# M_2_SoM_breakout_board_v0_3.net
KiCad netlist of a schematic drawn in EAGLE
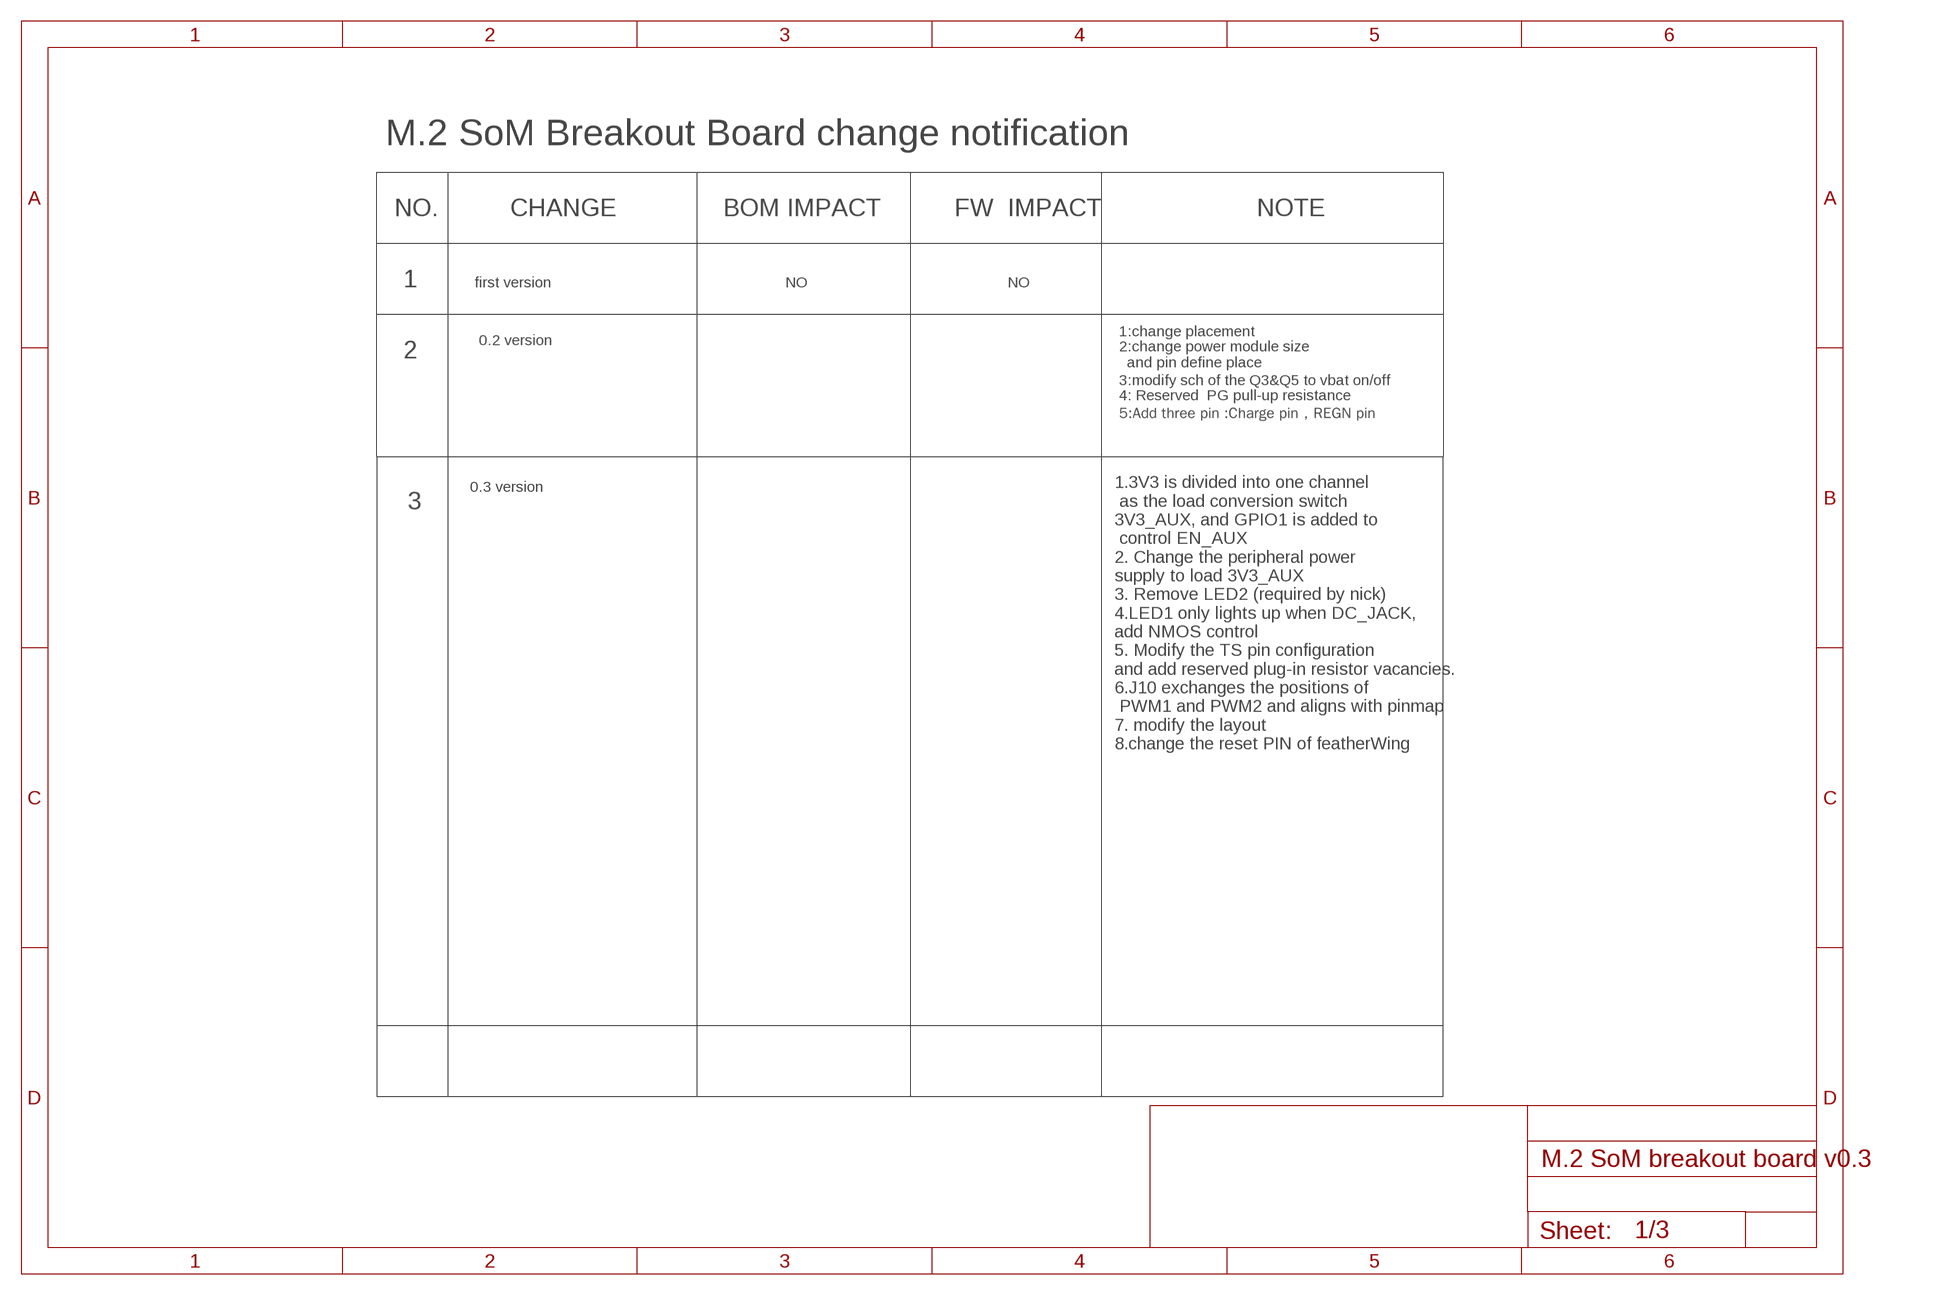
[diagram p0: schematic, sheet 1]
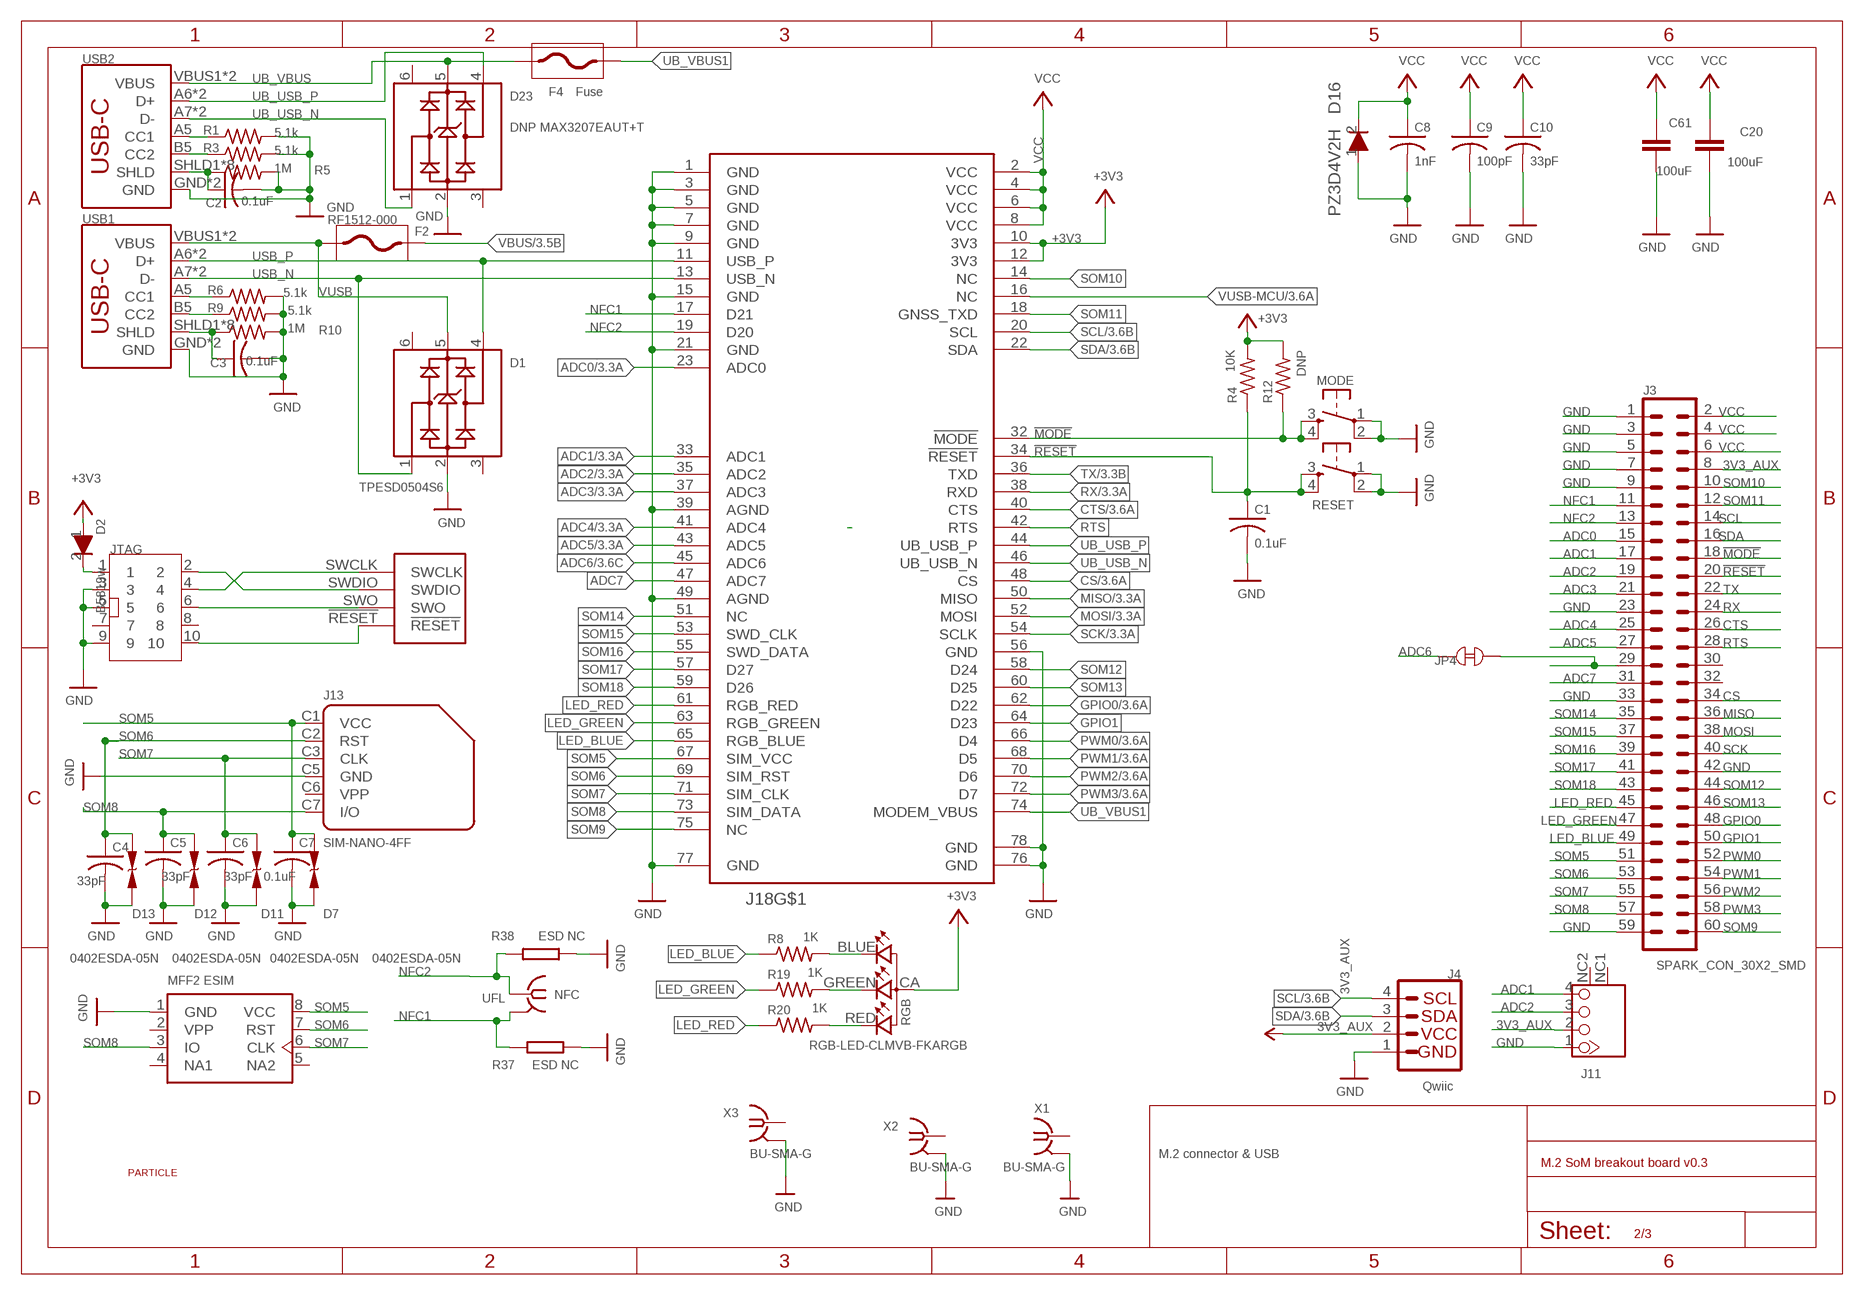
[diagram p1: schematic, sheet 2]
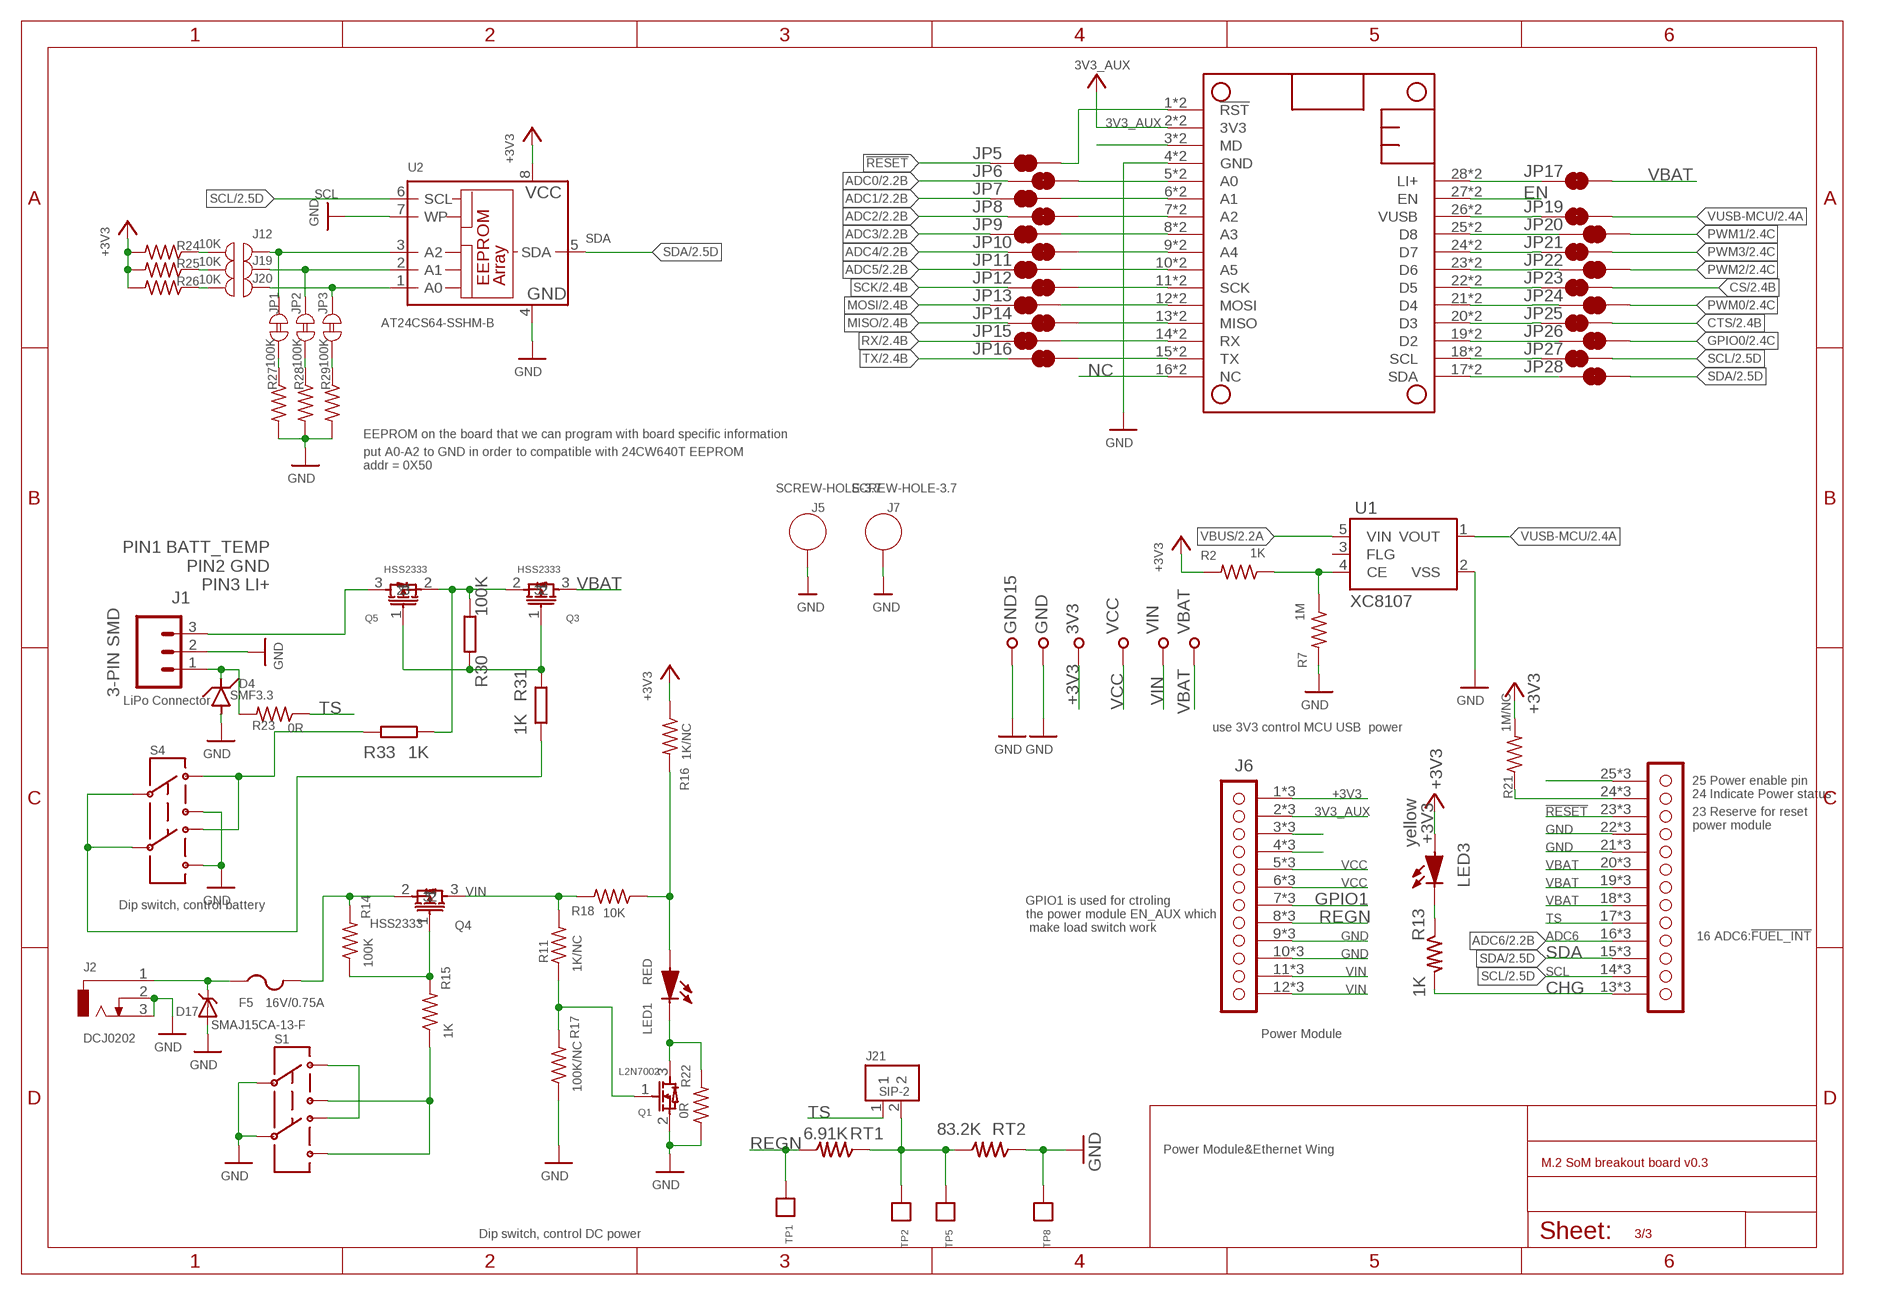
[diagram p2: schematic, sheet 3]

(export (version "E")
  (design (tool "Eeschema 10.0.6"))
  (components
    (comp (ref "C1")
      (value "0.1uF")
      (footprint "eagle-import:C0402_B")
      (libsource (lib "eagle-import") (part "C-US"))
    )
    (comp (ref "C2")
      (value "0.1uF")
      (footprint "eagle-import:C0402_B")
      (libsource (lib "eagle-import") (part "C-US"))
    )
    (comp (ref "C3")
      (value "0.1uF")
      (footprint "eagle-import:C0402_B")
      (libsource (lib "eagle-import") (part "C-US"))
    )
    (comp (ref "C4")
      (value "33pF")
      (footprint "eagle-import:C0402_B")
      (libsource (lib "eagle-import") (part "C-US"))
    )
    (comp (ref "C5")
      (value "33pF")
      (footprint "eagle-import:C0402_B")
      (libsource (lib "eagle-import") (part "C-US"))
    )
    (comp (ref "C6")
      (value "33pF")
      (footprint "eagle-import:C0402_B")
      (libsource (lib "eagle-import") (part "C-US"))
    )
    (comp (ref "C7")
      (value "0.1uF")
      (footprint "eagle-import:C0402_B")
      (libsource (lib "eagle-import") (part "C-US"))
    )
    (comp (ref "C8")
      (value "1nF")
      (footprint "eagle-import:C0402_B")
      (libsource (lib "eagle-import") (part "C-US"))
    )
    (comp (ref "C9")
      (value "100pF")
      (footprint "eagle-import:C0402_B")
      (libsource (lib "eagle-import") (part "C-US"))
    )
    (comp (ref "C10")
      (value "33pF")
      (footprint "eagle-import:C0402_B")
      (libsource (lib "eagle-import") (part "C-US"))
    )
    (comp (ref "C20")
      (value "100uF")
      (footprint "eagle-import:C1206K")
      (libsource (lib "eagle-import") (part "C-EUC1206K"))
    )
    (comp (ref "C61")
      (value "100uF")
      (footprint "eagle-import:C1206K")
      (libsource (lib "eagle-import") (part "C-EUC1206K"))
    )
    (comp (ref "D1")
      (value "TPESD0504S6")
      (footprint "eagle-import:SOT23-6")
      (fields (field (name "MFG") "MAXIM") (field (name "MPN") "MAX3207EAUT+T"))
      (libsource (lib "eagle-import") (part "MAX3207EAUT+T"))
    )
    (comp (ref "D2")
      (value "B5819w")
      (footprint "eagle-import:SOD-123")
      (libsource (lib "eagle-import") (part "DIODESOD123"))
    )
    (comp (ref "D7")
      (value "0402ESDA-05N")
      (footprint "eagle-import:C0402")
      (libsource (lib "eagle-import") (part "ESD"))
    )
    (comp (ref "D11")
      (value "0402ESDA-05N")
      (footprint "eagle-import:C0402")
      (libsource (lib "eagle-import") (part "ESD"))
    )
    (comp (ref "D12")
      (value "0402ESDA-05N")
      (footprint "eagle-import:C0402")
      (libsource (lib "eagle-import") (part "ESD"))
    )
    (comp (ref "D13")
      (value "0402ESDA-05N")
      (footprint "eagle-import:C0402")
      (libsource (lib "eagle-import") (part "ESD"))
    )
    (comp (ref "D16")
      (value "PZ3D4V2H")
      (footprint "eagle-import:SOD-323")
      (libsource (lib "eagle-import") (part "DIODESOD323"))
    )
    (comp (ref "D23")
      (value "DNP MAX3207EAUT+T")
      (footprint "eagle-import:SOT23-6")
      (fields (field (name "MFG") "MAXIM") (field (name "MPN") "MAX3207EAUT+T"))
      (libsource (lib "eagle-import") (part "MAX3207EAUT+T"))
    )
    (comp (ref "F2")
      (value "RF1512-000")
      (footprint "eagle-import:F0805")
      (libsource (lib "eagle-import") (part "FUSE"))
    )
    (comp (ref "F4")
      (value "Fuse")
      (footprint "eagle-import:F0805")
      (libsource (lib "eagle-import") (part "FUSE"))
    )
    (comp (ref "J3")
      (value "SPARK_CON_30X2_SMD")
      (footprint "eagle-import:SPARK_CON_30X2_SMD")
      (libsource (lib "eagle-import") (part "SPARK_CON_30X2_SMD"))
    )
    (comp (ref "J4")
      (value "QWIIC_CONNECTORJS-1MM")
      (footprint "eagle-import:1X04_1MM_RA")
      (libsource (lib "eagle-import") (part "QWIIC_CONNECTORJS-1MM"))
    )
    (comp (ref "J11")
      (value "WAFER-HY2.0-4PWB")
      (footprint "eagle-import:M.2-SOM-BREAKOUT-BOARD-V0.2-0228_WAFER-HY2.0-4PWB")
      (libsource (lib "eagle-import") (part "M.2-SOM-BREAKOUT-BOARD-V0.2-0228_WAFER-HY2.0-4PWB"))
    )
    (comp (ref "J13")
      (value "SIM-NANO-4FF")
      (footprint "eagle-import:GCT-SIM8100")
      (libsource (lib "eagle-import") (part "SIM-NANO-4FF"))
    )
    (comp (ref "J18")
      (value "PARTICLE-STUDIOS_M_SERIES_M.2KEY")
      (footprint "eagle-import:PARTICLE-STUDIOS_PARTICLE_M.2EKEY_3.65MM_DRILL")
      (libsource (lib "eagle-import") (part "PARTICLE-STUDIOS_M_SERIES_M.2KEY"))
    )
    (comp (ref "JP4")
      (value "TP_SHORT")
      (footprint "eagle-import:TP_SHORT")
      (libsource (lib "eagle-import") (part "TP_SHORT"))
    )
    (comp (ref "JTAG")
      (value "CONN5X2")
      (footprint "eagle-import:CONN5X2_1.27")
      (fields (field (name "MFG") "KAWEEI") (field (name "MPN") "P6014A-M2GC-030-10"))
      (libsource (lib "eagle-import") (part "CONN5X2"))
    )
    (comp (ref "MODE")
      (value "TAC_SWITCHSMD")
      (footprint "eagle-import:TACTILE_SWITCH_SMD")
      (fields (field (name "MFG") "HAOYU") (field (name "MPN") "TS-1185A-025C"))
      (libsource (lib "eagle-import") (part "TAC_SWITCHSMD"))
    )
    (comp (ref "NFC")
      (value "UFL")
      (footprint "eagle-import:IPEX-20279-001E")
      (libsource (lib "eagle-import") (part "IPEX-20279-001E"))
    )
    (comp (ref "R1")
      (value "5.1k")
      (footprint "eagle-import:R0402_B")
      (libsource (lib "eagle-import") (part "R-US_"))
    )
    (comp (ref "R3")
      (value "5.1k")
      (footprint "eagle-import:R0402_B")
      (libsource (lib "eagle-import") (part "R-US_"))
    )
    (comp (ref "R4")
      (value "10K")
      (footprint "eagle-import:R0402_B")
      (libsource (lib "eagle-import") (part "R-US_"))
    )
    (comp (ref "R5")
      (value "1M")
      (footprint "eagle-import:R0402_B")
      (libsource (lib "eagle-import") (part "R-US_"))
    )
    (comp (ref "R6")
      (value "5.1k")
      (footprint "eagle-import:R0402_B")
      (libsource (lib "eagle-import") (part "R-US_"))
    )
    (comp (ref "R8")
      (value "1K")
      (footprint "eagle-import:R0402_B")
      (libsource (lib "eagle-import") (part "R-US_"))
    )
    (comp (ref "R9")
      (value "5.1k")
      (footprint "eagle-import:R0402_B")
      (libsource (lib "eagle-import") (part "R-US_"))
    )
    (comp (ref "R10")
      (value "1M")
      (footprint "eagle-import:R0402_B")
      (libsource (lib "eagle-import") (part "R-US_"))
    )
    (comp (ref "R12")
      (value "DNP")
      (footprint "eagle-import:R0402_B")
      (libsource (lib "eagle-import") (part "R-US_"))
    )
    (comp (ref "R19")
      (value "1K")
      (footprint "eagle-import:R0402_B")
      (libsource (lib "eagle-import") (part "R-US_"))
    )
    (comp (ref "R20")
      (value "1K")
      (footprint "eagle-import:R0402_B")
      (libsource (lib "eagle-import") (part "R-US_"))
    )
    (comp (ref "R37")
      (value "ESD NC")
      (footprint "eagle-import:R-0402S")
      (libsource (lib "eagle-import") (part "RES0402S"))
    )
    (comp (ref "R38")
      (value "ESD NC")
      (footprint "eagle-import:R-0402S")
      (libsource (lib "eagle-import") (part "RES0402S"))
    )
    (comp (ref "RESET")
      (value "TAC_SWITCHSMD")
      (footprint "eagle-import:TACTILE_SWITCH_SMD")
      (fields (field (name "MFG") "HAOYU") (field (name "MPN") "TS-1185A-025C"))
      (libsource (lib "eagle-import") (part "TAC_SWITCHSMD"))
    )
    (comp (ref "RGB")
      (value "RGB-LED-CLMVB-FKARGB")
      (footprint "eagle-import:PLCC4-2MM-RGB")
      (libsource (lib "eagle-import") (part "RGB-LED-CLMVB-FKARGB"))
    )
    (comp (ref "U$6")
      (value "PARTICLE-LOGO")
      (footprint "eagle-import:PARTICLE-LOGO")
      (libsource (lib "eagle-import") (part "PARTICLE-LOGO"))
    )
    (comp (ref "U7")
      (value "NC")
      (footprint "eagle-import:MFF2")
      (libsource (lib "eagle-import") (part "ESIMSON8"))
    )
    (comp (ref "USB1")
      (value "USB_C16PIN")
      (footprint "eagle-import:USB-C-16P")
      (libsource (lib "eagle-import") (part "USB_C16PIN"))
    )
    (comp (ref "USB2")
      (value "USB_C16PIN")
      (footprint "eagle-import:USB-C-16P")
      (libsource (lib "eagle-import") (part "USB_C16PIN"))
    )
    (comp (ref "X1")
      (value "BU-SMA-G")
      (footprint "eagle-import:BU-SMA-G")
      (libsource (lib "eagle-import") (part "BU-SMA-G"))
    )
    (comp (ref "X2")
      (value "BU-SMA-G")
      (footprint "eagle-import:BU-SMA-G")
      (libsource (lib "eagle-import") (part "BU-SMA-G"))
    )
    (comp (ref "X3")
      (value "BU-SMA-G")
      (footprint "eagle-import:BU-SMA-G")
      (libsource (lib "eagle-import") (part "BU-SMA-G"))
    )
    (comp (ref "3V3")
      (value "TP-S2751-46R")
      (footprint "eagle-import:S2751-46R")
      (libsource (lib "eagle-import") (part "TP-S2751-46R"))
    )
    (comp (ref "D4")
      (value "SMF3.3")
      (footprint "eagle-import:SOD-123FL")
      (libsource (lib "eagle-import") (part "TVS-DIODE-SOD123FL"))
    )
    (comp (ref "D17")
      (value "SMAJ15CA-13-F")
      (footprint "eagle-import:SMADIODE")
      (libsource (lib "eagle-import") (part "DIODE-ZENER"))
    )
    (comp (ref "F5")
      (value "16V/0.75A")
      (footprint "eagle-import:1812")
      (libsource (lib "eagle-import") (part "PTCFUSE-1812"))
    )
    (comp (ref "GND")
      (value "TP-S2751-46R")
      (footprint "eagle-import:S2751-46R")
      (libsource (lib "eagle-import") (part "TP-S2751-46R"))
    )
    (comp (ref "GND15")
      (value "TP-S2751-46R")
      (footprint "eagle-import:S2751-46R")
      (libsource (lib "eagle-import") (part "TP-S2751-46R"))
    )
    (comp (ref "J1")
      (value "3-PIN SMD")
      (footprint "eagle-import:JST-3-SMD")
      (libsource (lib "eagle-import") (part "CONN_03JST-SMD"))
    )
    (comp (ref "J2")
      (value "DCJ0202")
      (footprint "eagle-import:DCJ0202")
      (libsource (lib "eagle-import") (part "DCJ0202"))
    )
    (comp (ref "J5")
      (value "SCREW-HOLE-3.7")
      (footprint "eagle-import:SCREW-HOLE-3.7")
      (libsource (lib "eagle-import") (part "SCREW-HOLE-3.7"))
    )
    (comp (ref "J6")
      (value "PARTICLE-SZ_PARTICLE-POWER-MODULE")
      (footprint "eagle-import:PARTICLE-SZ_PARTICLE-POWER-MODULE")
      (libsource (lib "eagle-import") (part "PARTICLE-SZ_PARTICLE-POWER-MODULE"))
    )
    (comp (ref "J7")
      (value "SCREW-HOLE-3.7")
      (footprint "eagle-import:SCREW-HOLE-3.7")
      (libsource (lib "eagle-import") (part "SCREW-HOLE-3.7"))
    )
    (comp (ref "J12")
      (value "TP_OPEN")
      (footprint "eagle-import:TP_OPEN")
      (libsource (lib "eagle-import") (part "TP_OPEN"))
    )
    (comp (ref "J19")
      (value "TP_OPEN")
      (footprint "eagle-import:TP_OPEN")
      (libsource (lib "eagle-import") (part "TP_OPEN"))
    )
    (comp (ref "J20")
      (value "TP_OPEN")
      (footprint "eagle-import:TP_OPEN")
      (libsource (lib "eagle-import") (part "TP_OPEN"))
    )
    (comp (ref "J21")
      (value "SIP-2")
      (footprint "eagle-import:SIP-2")
      (libsource (lib "eagle-import") (part "SIP-2"))
    )
    (comp (ref "JP1")
      (value "TP_SHORT")
      (footprint "eagle-import:TP_SHORT")
      (libsource (lib "eagle-import") (part "TP_SHORT"))
    )
    (comp (ref "JP2")
      (value "TP_SHORT")
      (footprint "eagle-import:TP_SHORT")
      (libsource (lib "eagle-import") (part "TP_SHORT"))
    )
    (comp (ref "JP3")
      (value "TP_SHORT")
      (footprint "eagle-import:TP_SHORT")
      (libsource (lib "eagle-import") (part "TP_SHORT"))
    )
    (comp (ref "JP5")
      (value "JUMPER-SMT_2_NC_TRACE_NO-SILK")
      (footprint "eagle-import:SMT-JUMPER_2_NC_TRACE_NO-SILK")
      (libsource (lib "eagle-import") (part "JUMPER-SMT_2_NC_TRACE_NO-SILK"))
    )
    (comp (ref "JP6")
      (value "JUMPER-SMT_2_NC_TRACE_NO-SILK")
      (footprint "eagle-import:SMT-JUMPER_2_NC_TRACE_NO-SILK")
      (libsource (lib "eagle-import") (part "JUMPER-SMT_2_NC_TRACE_NO-SILK"))
    )
    (comp (ref "JP7")
      (value "JUMPER-SMT_2_NC_TRACE_NO-SILK")
      (footprint "eagle-import:SMT-JUMPER_2_NC_TRACE_NO-SILK")
      (libsource (lib "eagle-import") (part "JUMPER-SMT_2_NC_TRACE_NO-SILK"))
    )
    (comp (ref "JP8")
      (value "JUMPER-SMT_2_NC_TRACE_NO-SILK")
      (footprint "eagle-import:SMT-JUMPER_2_NC_TRACE_NO-SILK")
      (libsource (lib "eagle-import") (part "JUMPER-SMT_2_NC_TRACE_NO-SILK"))
    )
    (comp (ref "JP9")
      (value "JUMPER-SMT_2_NC_TRACE_NO-SILK")
      (footprint "eagle-import:SMT-JUMPER_2_NC_TRACE_NO-SILK")
      (libsource (lib "eagle-import") (part "JUMPER-SMT_2_NC_TRACE_NO-SILK"))
    )
    (comp (ref "JP10")
      (value "JUMPER-SMT_2_NC_TRACE_NO-SILK")
      (footprint "eagle-import:SMT-JUMPER_2_NC_TRACE_NO-SILK")
      (libsource (lib "eagle-import") (part "JUMPER-SMT_2_NC_TRACE_NO-SILK"))
    )
    (comp (ref "JP11")
      (value "JUMPER-SMT_2_NC_TRACE_NO-SILK")
      (footprint "eagle-import:SMT-JUMPER_2_NC_TRACE_NO-SILK")
      (libsource (lib "eagle-import") (part "JUMPER-SMT_2_NC_TRACE_NO-SILK"))
    )
    (comp (ref "JP12")
      (value "JUMPER-SMT_2_NC_TRACE_NO-SILK")
      (footprint "eagle-import:SMT-JUMPER_2_NC_TRACE_NO-SILK")
      (libsource (lib "eagle-import") (part "JUMPER-SMT_2_NC_TRACE_NO-SILK"))
    )
    (comp (ref "JP13")
      (value "JUMPER-SMT_2_NC_TRACE_NO-SILK")
      (footprint "eagle-import:SMT-JUMPER_2_NC_TRACE_NO-SILK")
      (libsource (lib "eagle-import") (part "JUMPER-SMT_2_NC_TRACE_NO-SILK"))
    )
    (comp (ref "JP14")
      (value "JUMPER-SMT_2_NC_TRACE_NO-SILK")
      (footprint "eagle-import:SMT-JUMPER_2_NC_TRACE_NO-SILK")
      (libsource (lib "eagle-import") (part "JUMPER-SMT_2_NC_TRACE_NO-SILK"))
    )
    (comp (ref "JP15")
      (value "JUMPER-SMT_2_NC_TRACE_NO-SILK")
      (footprint "eagle-import:SMT-JUMPER_2_NC_TRACE_NO-SILK")
      (libsource (lib "eagle-import") (part "JUMPER-SMT_2_NC_TRACE_NO-SILK"))
    )
    (comp (ref "JP16")
      (value "JUMPER-SMT_2_NC_TRACE_NO-SILK")
      (footprint "eagle-import:SMT-JUMPER_2_NC_TRACE_NO-SILK")
      (libsource (lib "eagle-import") (part "JUMPER-SMT_2_NC_TRACE_NO-SILK"))
    )
    (comp (ref "JP17")
      (value "JUMPER-SMT_2_NC_TRACE_NO-SILK")
      (footprint "eagle-import:SMT-JUMPER_2_NC_TRACE_NO-SILK")
      (libsource (lib "eagle-import") (part "JUMPER-SMT_2_NC_TRACE_NO-SILK"))
    )
    (comp (ref "JP19")
      (value "JUMPER-SMT_2_NC_TRACE_NO-SILK")
      (footprint "eagle-import:SMT-JUMPER_2_NC_TRACE_NO-SILK")
      (libsource (lib "eagle-import") (part "JUMPER-SMT_2_NC_TRACE_NO-SILK"))
    )
    (comp (ref "JP20")
      (value "JUMPER-SMT_2_NC_TRACE_NO-SILK")
      (footprint "eagle-import:SMT-JUMPER_2_NC_TRACE_NO-SILK")
      (libsource (lib "eagle-import") (part "JUMPER-SMT_2_NC_TRACE_NO-SILK"))
    )
    (comp (ref "JP21")
      (value "JUMPER-SMT_2_NC_TRACE_NO-SILK")
      (footprint "eagle-import:SMT-JUMPER_2_NC_TRACE_NO-SILK")
      (libsource (lib "eagle-import") (part "JUMPER-SMT_2_NC_TRACE_NO-SILK"))
    )
    (comp (ref "JP22")
      (value "JUMPER-SMT_2_NC_TRACE_NO-SILK")
      (footprint "eagle-import:SMT-JUMPER_2_NC_TRACE_NO-SILK")
      (libsource (lib "eagle-import") (part "JUMPER-SMT_2_NC_TRACE_NO-SILK"))
    )
    (comp (ref "JP23")
      (value "JUMPER-SMT_2_NC_TRACE_NO-SILK")
      (footprint "eagle-import:SMT-JUMPER_2_NC_TRACE_NO-SILK")
      (libsource (lib "eagle-import") (part "JUMPER-SMT_2_NC_TRACE_NO-SILK"))
    )
    (comp (ref "JP24")
      (value "JUMPER-SMT_2_NC_TRACE_NO-SILK")
      (footprint "eagle-import:SMT-JUMPER_2_NC_TRACE_NO-SILK")
      (libsource (lib "eagle-import") (part "JUMPER-SMT_2_NC_TRACE_NO-SILK"))
    )
    (comp (ref "JP25")
      (value "JUMPER-SMT_2_NC_TRACE_NO-SILK")
      (footprint "eagle-import:SMT-JUMPER_2_NC_TRACE_NO-SILK")
      (libsource (lib "eagle-import") (part "JUMPER-SMT_2_NC_TRACE_NO-SILK"))
    )
    (comp (ref "JP26")
      (value "JUMPER-SMT_2_NC_TRACE_NO-SILK")
      (footprint "eagle-import:SMT-JUMPER_2_NC_TRACE_NO-SILK")
      (libsource (lib "eagle-import") (part "JUMPER-SMT_2_NC_TRACE_NO-SILK"))
    )
    (comp (ref "JP27")
      (value "JUMPER-SMT_2_NC_TRACE_NO-SILK")
      (footprint "eagle-import:SMT-JUMPER_2_NC_TRACE_NO-SILK")
      (libsource (lib "eagle-import") (part "JUMPER-SMT_2_NC_TRACE_NO-SILK"))
    )
    (comp (ref "JP28")
      (value "JUMPER-SMT_2_NC_TRACE_NO-SILK")
      (footprint "eagle-import:SMT-JUMPER_2_NC_TRACE_NO-SILK")
      (libsource (lib "eagle-import") (part "JUMPER-SMT_2_NC_TRACE_NO-SILK"))
    )
    (comp (ref "LED1")
      (value "RED")
      (footprint "eagle-import:LED0603")
      (libsource (lib "eagle-import") (part "LED"))
    )
    (comp (ref "LED3")
      (value "yellow")
      (footprint "eagle-import:LED0603")
      (libsource (lib "eagle-import") (part "LED"))
    )
    (comp (ref "MS1")
      (value "PARTICLE_MESH_SMTDUAL")
      (footprint "eagle-import:FEATHERWING_SMT2")
      (libsource (lib "eagle-import") (part "PARTICLE_MESH_SMTDUAL"))
    )
    (comp (ref "Q1")
      (value "L2N7002")
      (footprint "eagle-import:SOT323")
      (libsource (lib "eagle-import") (part "NMOSSOT323"))
    )
    (comp (ref "Q3")
      (value "HSS2333")
      (footprint "eagle-import:SOT-23")
      (libsource (lib "eagle-import") (part "PMOS"))
    )
    (comp (ref "Q4")
      (value "HSS2333")
      (footprint "eagle-import:SOT-23")
      (libsource (lib "eagle-import") (part "PMOS"))
    )
    (comp (ref "Q5")
      (value "HSS2333")
      (footprint "eagle-import:SOT-23")
      (libsource (lib "eagle-import") (part "PMOS"))
    )
    (comp (ref "R2")
      (value "1K")
      (footprint "eagle-import:R0402_B")
      (libsource (lib "eagle-import") (part "R-US_"))
    )
    (comp (ref "R7")
      (value "1M")
      (footprint "eagle-import:R0402_B")
      (libsource (lib "eagle-import") (part "R-US_"))
    )
    (comp (ref "R11")
      (value "1K/NC")
      (footprint "eagle-import:R0402_B")
      (libsource (lib "eagle-import") (part "R-US_"))
    )
    (comp (ref "R13")
      (value "1K")
      (footprint "eagle-import:R-0402S")
      (libsource (lib "eagle-import") (part "particle SZ_RES0402S"))
    )
    (comp (ref "R14")
      (value "100K")
      (footprint "eagle-import:R0402_B")
      (libsource (lib "eagle-import") (part "R-US_"))
    )
    (comp (ref "R15")
      (value "1K")
      (footprint "eagle-import:R0402_B")
      (libsource (lib "eagle-import") (part "R-US_"))
    )
    (comp (ref "R16")
      (value "1K/NC")
      (footprint "eagle-import:R0402_B")
      (libsource (lib "eagle-import") (part "R-US_"))
    )
    (comp (ref "R17")
      (value "100K/NC")
      (footprint "eagle-import:R0402_B")
      (libsource (lib "eagle-import") (part "R-US_"))
    )
    (comp (ref "R18")
      (value "10K")
      (footprint "eagle-import:R0402_B")
      (libsource (lib "eagle-import") (part "R-US_"))
    )
    (comp (ref "R21")
      (value "1M/NC")
      (footprint "eagle-import:R0402_B")
      (libsource (lib "eagle-import") (part "R-US_"))
    )
    (comp (ref "R22")
      (value "0R")
      (footprint "eagle-import:R0402_B")
      (libsource (lib "eagle-import") (part "R-US_"))
    )
    (comp (ref "R23")
      (value "0R")
      (footprint "eagle-import:R0402_B")
      (libsource (lib "eagle-import") (part "R-US_"))
    )
    (comp (ref "R24")
      (value "10K")
      (footprint "eagle-import:R0402_B")
      (libsource (lib "eagle-import") (part "R-US_"))
    )
    (comp (ref "R25")
      (value "10K")
      (footprint "eagle-import:R0402_B")
      (libsource (lib "eagle-import") (part "R-US_"))
    )
    (comp (ref "R26")
      (value "10K")
      (footprint "eagle-import:R0402_B")
      (libsource (lib "eagle-import") (part "R-US_"))
    )
    (comp (ref "R27")
      (value "100K")
      (footprint "eagle-import:R0402_B")
      (libsource (lib "eagle-import") (part "R-US_"))
    )
    (comp (ref "R28")
      (value "100K")
      (footprint "eagle-import:R0402_B")
      (libsource (lib "eagle-import") (part "R-US_"))
    )
    (comp (ref "R29")
      (value "100K")
      (footprint "eagle-import:R0402_B")
      (libsource (lib "eagle-import") (part "R-US_"))
    )
    (comp (ref "R30")
      (value "100K")
      (footprint "eagle-import:R0603")
      (libsource (lib "eagle-import") (part "RESR0603"))
    )
    (comp (ref "R31")
      (value "1K")
      (footprint "eagle-import:R-0402S")
      (libsource (lib "eagle-import") (part "RES0402S"))
    )
    (comp (ref "R33")
      (value "1K")
      (footprint "eagle-import:R-0402S")
      (libsource (lib "eagle-import") (part "RES0402S"))
    )
    (comp (ref "RT1")
      (value "6.91K")
      (footprint "eagle-import:R-0603A")
      (libsource (lib "eagle-import") (part "RESR0603A"))
    )
    (comp (ref "RT2")
      (value "83.2K")
      (footprint "eagle-import:R-0603A")
      (libsource (lib "eagle-import") (part "RESR0603A"))
    )
    (comp (ref "S1")
      (value "SWITCH-DPDT")
      (footprint "eagle-import:SWITCH-2.5X3.2-6")
      (libsource (lib "eagle-import") (part "SWITCH-DPDT"))
    )
    (comp (ref "S4")
      (value "SWITCH-DPDT")
      (footprint "eagle-import:SWITCH-2.5X3.2-6")
      (libsource (lib "eagle-import") (part "SWITCH-DPDT"))
    )
    (comp (ref "TP1")
      (value "TPTPEB")
      (footprint "eagle-import:TPEB")
      (libsource (lib "eagle-import") (part "TPTPEB"))
    )
    (comp (ref "TP2")
      (value "TPTPEB")
      (footprint "eagle-import:TPEB")
      (libsource (lib "eagle-import") (part "TPTPEB"))
    )
    (comp (ref "TP5")
      (value "TPTPEB")
      (footprint "eagle-import:TPEB")
      (libsource (lib "eagle-import") (part "TPTPEB"))
    )
    (comp (ref "TP8")
      (value "TPTPEB")
      (footprint "eagle-import:TPEB")
      (libsource (lib "eagle-import") (part "TPTPEB"))
    )
    (comp (ref "U1")
      (value "XC8107")
      (footprint "eagle-import:SOT25")
      (libsource (lib "eagle-import") (part "XC8107SOT25"))
    )
    (comp (ref "U2")
      (value "AT24CS64-SSHM-B")
      (footprint "eagle-import:SO-08")
      (fields (field (name "MF") "MICROCHIP") (field (name "MPN") "24AA01/SN"))
      (libsource (lib "eagle-import") (part "24SNAA01"))
    )
    (comp (ref "VBAT")
      (value "TP-S2751-46R")
      (footprint "eagle-import:S2751-46R")
      (libsource (lib "eagle-import") (part "TP-S2751-46R"))
    )
    (comp (ref "VCC")
      (value "TP-S2751-46R")
      (footprint "eagle-import:S2751-46R")
      (libsource (lib "eagle-import") (part "TP-S2751-46R"))
    )
    (comp (ref "VIN")
      (value "TP-S2751-46R")
      (footprint "eagle-import:S2751-46R")
      (libsource (lib "eagle-import") (part "TP-S2751-46R"))
    )
  )
  (nets
    (net (code "1") (name "+3V3") (class "Default")
      (node (ref "3V3") (pin "1") (pinfunction "TP_1") (pintype "bidirectional"))
      (node (ref "D2") (pin "1") (pinfunction "P$1_1") (pintype "bidirectional"))
      (node (ref "J18") (pin "10") (pinfunction "3V3_10") (pintype "power_in"))
      (node (ref "J18") (pin "12") (pinfunction "3V3_12") (pintype "power_in"))
      (node (ref "J6") (pin "1") (pinfunction "3V3_1") (pintype "passive"))
      (node (ref "J6") (pin "@1") (pinfunction "3V3_@1") (pintype "passive"))
      (node (ref "J6") (pin "P$1") (pinfunction "3V3_P$1") (pintype "passive"))
      (node (ref "LED3") (pin "1") (pinfunction "A_1") (pintype "bidirectional"))
      (node (ref "R12") (pin "2") (pinfunction "2_2") (pintype "passive"))
      (node (ref "R16") (pin "1") (pinfunction "1_1") (pintype "passive"))
      (node (ref "R2") (pin "2") (pinfunction "2_2") (pintype "passive"))
      (node (ref "R21") (pin "2") (pinfunction "2_2") (pintype "passive"))
      (node (ref "R24") (pin "2") (pinfunction "2_2") (pintype "passive"))
      (node (ref "R25") (pin "2") (pinfunction "2_2") (pintype "passive"))
      (node (ref "R26") (pin "2") (pinfunction "2_2") (pintype "passive"))
      (node (ref "R4") (pin "2") (pinfunction "2_2") (pintype "passive"))
      (node (ref "RGB") (pin "CA") (pinfunction "1_CA") (pintype "passive"))
      (node (ref "U2") (pin "8") (pinfunction "VCC_8") (pintype "power_in"))
    )
    (net (code "2") (name "3V3_AUX") (class "Default")
      (node (ref "J11") (pin "2") (pinfunction "2_2") (pintype "bidirectional"))
      (node (ref "J3") (pin "8") (pinfunction "8_8") (pintype "passive"))
      (node (ref "J4") (pin "2") (pinfunction "2_2") (pintype "power_in"))
      (node (ref "J6") (pin "2") (pinfunction "3V3_2") (pintype "passive"))
      (node (ref "J6") (pin "@2") (pinfunction "3V3_@2") (pintype "passive"))
      (node (ref "J6") (pin "P$2") (pinfunction "3V3_P$2") (pintype "passive"))
      (node (ref "MS1") (pin "2") (pinfunction "3V3_2") (pintype "power_in"))
      (node (ref "MS1") (pin "2'") (pinfunction "3V3_2'") (pintype "power_in"))
    )
    (net (code "3") (name "ADC0") (class "Default")
      (node (ref "J18") (pin "23") (pinfunction "ADC0_23") (pintype "bidirectional"))
      (node (ref "J3") (pin "15") (pinfunction "15_15") (pintype "passive"))
      (node (ref "JP6") (pin "1") (pinfunction "1_1") (pintype "passive"))
    )
    (net (code "4") (name "ADC1") (class "Default")
      (node (ref "J11") (pin "4") (pinfunction "4_4") (pintype "bidirectional"))
      (node (ref "J18") (pin "33") (pinfunction "ADC1_33") (pintype "bidirectional"))
      (node (ref "J3") (pin "17") (pinfunction "17_17") (pintype "passive"))
      (node (ref "JP7") (pin "1") (pinfunction "1_1") (pintype "passive"))
    )
    (net (code "5") (name "ADC2") (class "Default")
      (node (ref "J11") (pin "3") (pinfunction "3_3") (pintype "bidirectional"))
      (node (ref "J18") (pin "35") (pinfunction "ADC2_35") (pintype "bidirectional"))
      (node (ref "J3") (pin "19") (pinfunction "19_19") (pintype "passive"))
      (node (ref "JP8") (pin "1") (pinfunction "1_1") (pintype "passive"))
    )
    (net (code "6") (name "ADC3") (class "Default")
      (node (ref "J18") (pin "37") (pinfunction "ADC3_37") (pintype "bidirectional"))
      (node (ref "J3") (pin "21") (pinfunction "21_21") (pintype "passive"))
      (node (ref "JP9") (pin "1") (pinfunction "1_1") (pintype "passive"))
    )
    (net (code "7") (name "ADC4") (class "Default")
      (node (ref "J18") (pin "41") (pinfunction "ADC4_41") (pintype "bidirectional"))
      (node (ref "J3") (pin "25") (pinfunction "25_25") (pintype "passive"))
      (node (ref "JP10") (pin "1") (pinfunction "1_1") (pintype "passive"))
    )
    (net (code "8") (name "ADC5") (class "Default")
      (node (ref "J18") (pin "43") (pinfunction "ADC5_43") (pintype "bidirectional"))
      (node (ref "J3") (pin "27") (pinfunction "27_27") (pintype "passive"))
      (node (ref "JP11") (pin "1") (pinfunction "1_1") (pintype "passive"))
    )
    (net (code "9") (name "ADC6") (class "Default")
      (node (ref "J18") (pin "45") (pinfunction "ADC6_45") (pintype "bidirectional"))
      (node (ref "J6") (pin "16") (pinfunction "~{FUEL-INT}_16") (pintype "passive"))
      (node (ref "J6") (pin "@16") (pinfunction "~{FUEL-INT}_@16") (pintype "passive"))
      (node (ref "J6") (pin "P$16") (pinfunction "~{FUEL-INT}_P$16") (pintype "passive"))
      (node (ref "JP4") (pin "2") (pinfunction "2_2") (pintype "bidirectional"))
    )
    (net (code "10") (name "ADC7") (class "Default")
      (node (ref "J18") (pin "47") (pinfunction "ADC7_47") (pintype "bidirectional"))
      (node (ref "J3") (pin "31") (pinfunction "31_31") (pintype "passive"))
    )
    (net (code "11") (name "CHG") (class "Default")
      (node (ref "J6") (pin "13") (pinfunction "CHG_13") (pintype "passive"))
      (node (ref "J6") (pin "@13") (pinfunction "CHG_@13") (pintype "passive"))
      (node (ref "J6") (pin "P$13") (pinfunction "CHG_P$13") (pintype "passive"))
      (node (ref "R13") (pin "2") (pinfunction "2_2") (pintype "bidirectional"))
    )
    (net (code "12") (name "CS") (class "Default")
      (node (ref "J18") (pin "48") (pinfunction "CS_48") (pintype "bidirectional"))
      (node (ref "J3") (pin "34") (pinfunction "34_34") (pintype "passive"))
      (node (ref "JP23") (pin "2") (pinfunction "2_2") (pintype "passive"))
    )
    (net (code "13") (name "CTS") (class "Default")
      (node (ref "J18") (pin "40") (pinfunction "CTS_40") (pintype "bidirectional"))
      (node (ref "J3") (pin "26") (pinfunction "26_26") (pintype "passive"))
      (node (ref "JP25") (pin "2") (pinfunction "2_2") (pintype "passive"))
    )
    (net (code "14") (name "EN") (class "Default")
      (node (ref "MS1") (pin "27") (pinfunction "EN_27") (pintype "passive"))
      (node (ref "MS1") (pin "27'") (pinfunction "EN_27'") (pintype "passive"))
    )
    (net (code "15") (name "GND") (class "Default")
      (node (ref "C1") (pin "2") (pinfunction "2_2") (pintype "passive"))
      (node (ref "C10") (pin "2") (pinfunction "2_2") (pintype "passive"))
      (node (ref "C2") (pin "2") (pinfunction "2_2") (pintype "passive"))
      (node (ref "C20") (pin "2") (pinfunction "2_2") (pintype "passive"))
      (node (ref "C3") (pin "2") (pinfunction "2_2") (pintype "passive"))
      (node (ref "C4") (pin "2") (pinfunction "2_2") (pintype "passive"))
      (node (ref "C5") (pin "2") (pinfunction "2_2") (pintype "passive"))
      (node (ref "C6") (pin "2") (pinfunction "2_2") (pintype "passive"))
      (node (ref "C61") (pin "2") (pinfunction "2_2") (pintype "passive"))
      (node (ref "C7") (pin "2") (pinfunction "2_2") (pintype "passive"))
      (node (ref "C8") (pin "2") (pinfunction "2_2") (pintype "passive"))
      (node (ref "C9") (pin "2") (pinfunction "2_2") (pintype "passive"))
      (node (ref "D1") (pin "2") (pinfunction "2_2") (pintype "bidirectional"))
      (node (ref "D11") (pin "1") (pinfunction "1_1") (pintype "bidirectional"))
      (node (ref "D12") (pin "1") (pinfunction "1_1") (pintype "bidirectional"))
      (node (ref "D13") (pin "1") (pinfunction "1_1") (pintype "bidirectional"))
      (node (ref "D16") (pin "1") (pinfunction "P$1_1") (pintype "bidirectional"))
      (node (ref "D17") (pin "A") (pinfunction "A_A") (pintype "passive"))
      (node (ref "D23") (pin "2") (pinfunction "2_2") (pintype "bidirectional"))
      (node (ref "D4") (pin "A") (pinfunction "A_A") (pintype "passive"))
      (node (ref "D7") (pin "1") (pinfunction "1_1") (pintype "bidirectional"))
      (node (ref "GND") (pin "1") (pinfunction "TP_1") (pintype "bidirectional"))
      (node (ref "GND15") (pin "1") (pinfunction "TP_1") (pintype "bidirectional"))
      (node (ref "J1") (pin "2") (pinfunction "2_2") (pintype "passive"))
      (node (ref "J11") (pin "1") (pinfunction "1_1") (pintype "bidirectional"))
      (node (ref "J13") (pin "C5") (pinfunction "GND_C5") (pintype "passive"))
      (node (ref "J18") (pin "1") (pinfunction "GND_1") (pintype "power_in"))
      (node (ref "J18") (pin "15") (pinfunction "GND_15") (pintype "power_in"))
      (node (ref "J18") (pin "21") (pinfunction "GND_21") (pintype "power_in"))
      (node (ref "J18") (pin "3") (pinfunction "GND_3") (pintype "power_in"))
      (node (ref "J18") (pin "39") (pinfunction "AGND_39") (pintype "power_in"))
      (node (ref "J18") (pin "49") (pinfunction "AGND_49") (pintype "power_in"))
      (node (ref "J18") (pin "5") (pinfunction "GND_5") (pintype "power_in"))
      (node (ref "J18") (pin "56") (pinfunction "GND_56") (pintype "power_in"))
      (node (ref "J18") (pin "7") (pinfunction "GND_7") (pintype "power_in"))
      (node (ref "J18") (pin "76") (pinfunction "GND_76") (pintype "power_in"))
      (node (ref "J18") (pin "77") (pinfunction "GND_77") (pintype "power_in"))
      (node (ref "J18") (pin "78") (pinfunction "GND_78") (pintype "power_in"))
      (node (ref "J18") (pin "9") (pinfunction "GND_9") (pintype "power_in"))
      (node (ref "J2") (pin "2") (pinfunction "2_2") (pintype "passive"))
      (node (ref "J2") (pin "3") (pinfunction "3_3") (pintype "passive"))
      (node (ref "J3") (pin "1") (pinfunction "1_1") (pintype "passive"))
      (node (ref "J3") (pin "23") (pinfunction "23_23") (pintype "passive"))
      (node (ref "J3") (pin "3") (pinfunction "3_3") (pintype "passive"))
      (node (ref "J3") (pin "33") (pinfunction "33_33") (pintype "passive"))
      (node (ref "J3") (pin "42") (pinfunction "42_42") (pintype "passive"))
      (node (ref "J3") (pin "5") (pinfunction "5_5") (pintype "passive"))
      (node (ref "J3") (pin "59") (pinfunction "59_59") (pintype "passive"))
      (node (ref "J3") (pin "7") (pinfunction "7_7") (pintype "passive"))
      (node (ref "J3") (pin "9") (pinfunction "9_9") (pintype "passive"))
      (node (ref "J4") (pin "1") (pinfunction "1_1") (pintype "power_in"))
      (node (ref "J5") (pin "P$1") (pinfunction "GND_P$1") (pintype "bidirectional"))
      (node (ref "J6") (pin "10") (pinfunction "GND_10") (pintype "passive"))
      (node (ref "J6") (pin "21") (pinfunction "GND_21") (pintype "passive"))
      (node (ref "J6") (pin "22") (pinfunction "GND_22") (pintype "passive"))
      (node (ref "J6") (pin "9") (pinfunction "GND_9") (pintype "passive"))
      (node (ref "J6") (pin "@10") (pinfunction "GND_@10") (pintype "passive"))
      (node (ref "J6") (pin "@21") (pinfunction "GND_@21") (pintype "passive"))
      (node (ref "J6") (pin "@22") (pinfunction "GND_@22") (pintype "passive"))
      (node (ref "J6") (pin "@9") (pinfunction "GND_@9") (pintype "passive"))
      (node (ref "J6") (pin "P$10") (pinfunction "GND_P$10") (pintype "passive"))
      (node (ref "J6") (pin "P$21") (pinfunction "GND_P$21") (pintype "passive"))
      (node (ref "J6") (pin "P$22") (pinfunction "GND_P$22") (pintype "passive"))
      (node (ref "J6") (pin "P$9") (pinfunction "GND_P$9") (pintype "passive"))
      (node (ref "J7") (pin "P$1") (pinfunction "GND_P$1") (pintype "bidirectional"))
      (node (ref "JTAG") (pin "3") (pinfunction "3_3") (pintype "bidirectional"))
      (node (ref "JTAG") (pin "5") (pinfunction "5_5") (pintype "bidirectional"))
      (node (ref "JTAG") (pin "9") (pinfunction "9_9") (pintype "bidirectional"))
      (node (ref "MODE") (pin "1") (pinfunction "1_1") (pintype "passive"))
      (node (ref "MODE") (pin "2") (pinfunction "2_2") (pintype "passive"))
      (node (ref "MS1") (pin "4") (pinfunction "GND_4") (pintype "power_in"))
      (node (ref "MS1") (pin "4'") (pinfunction "GND_4'") (pintype "power_in"))
      (node (ref "Q1") (pin "2") (pinfunction "2_2") (pintype "bidirectional"))
      (node (ref "R1") (pin "2") (pinfunction "2_2") (pintype "passive"))
      (node (ref "R10") (pin "2") (pinfunction "2_2") (pintype "passive"))
      (node (ref "R17") (pin "1") (pinfunction "1_1") (pintype "passive"))
      (node (ref "R22") (pin "1") (pinfunction "1_1") (pintype "passive"))
      (node (ref "R27") (pin "2") (pinfunction "2_2") (pintype "passive"))
      (node (ref "R28") (pin "2") (pinfunction "2_2") (pintype "passive"))
      (node (ref "R29") (pin "2") (pinfunction "2_2") (pintype "passive"))
      (node (ref "R3") (pin "2") (pinfunction "2_2") (pintype "passive"))
      (node (ref "R37") (pin "2") (pinfunction "2_2") (pintype "bidirectional"))
      (node (ref "R38") (pin "1") (pinfunction "1_1") (pintype "bidirectional"))
      (node (ref "R5") (pin "2") (pinfunction "2_2") (pintype "passive"))
      (node (ref "R6") (pin "2") (pinfunction "2_2") (pintype "passive"))
      (node (ref "R7") (pin "2") (pinfunction "2_2") (pintype "passive"))
      (node (ref "R9") (pin "2") (pinfunction "2_2") (pintype "passive"))
      (node (ref "RESET") (pin "1") (pinfunction "1_1") (pintype "passive"))
      (node (ref "RESET") (pin "2") (pinfunction "2_2") (pintype "passive"))
      (node (ref "RT2") (pin "1") (pinfunction "1_1") (pintype "bidirectional"))
      (node (ref "S1") (pin "2") (pinfunction "2_2") (pintype "bidirectional"))
      (node (ref "S1") (pin "5") (pinfunction "5_5") (pintype "bidirectional"))
      (node (ref "S4") (pin "3") (pinfunction "3_3") (pintype "bidirectional"))
      (node (ref "S4") (pin "6") (pinfunction "6_6") (pintype "bidirectional"))
      (node (ref "TP8") (pin "1") (pinfunction "1_1") (pintype "bidirectional"))
      (node (ref "U1") (pin "2") (pinfunction "VSS_2") (pintype "power_in"))
      (node (ref "U2") (pin "4") (pinfunction "GND_4") (pintype "power_in"))
      (node (ref "U2") (pin "7") (pinfunction "WP_7") (pintype "input"))
      (node (ref "U7") (pin "1") (pinfunction "GND_1") (pintype "power_in"))
      (node (ref "USB1") (pin "GND") (pinfunction "GND_GND") (pintype "bidirectional"))
      (node (ref "USB1") (pin "GND2") (pinfunction "GND_GND2") (pintype "bidirectional"))
      (node (ref "USB2") (pin "GND") (pinfunction "GND_GND") (pintype "bidirectional"))
      (node (ref "USB2") (pin "GND2") (pinfunction "GND_GND2") (pintype "bidirectional"))
      (node (ref "X1") (pin "2") (pinfunction "2_2") (pintype "passive"))
      (node (ref "X1") (pin "3") (pinfunction "2_3") (pintype "passive"))
      (node (ref "X1") (pin "4") (pinfunction "2_4") (pintype "passive"))
      (node (ref "X1") (pin "5") (pinfunction "2_5") (pintype "passive"))
      (node (ref "X2") (pin "2") (pinfunction "2_2") (pintype "passive"))
      (node (ref "X2") (pin "3") (pinfunction "2_3") (pintype "passive"))
      (node (ref "X2") (pin "4") (pinfunction "2_4") (pintype "passive"))
      (node (ref "X2") (pin "5") (pinfunction "2_5") (pintype "passive"))
      (node (ref "X3") (pin "2") (pinfunction "2_2") (pintype "passive"))
      (node (ref "X3") (pin "3") (pinfunction "2_3") (pintype "passive"))
      (node (ref "X3") (pin "4") (pinfunction "2_4") (pintype "passive"))
      (node (ref "X3") (pin "5") (pinfunction "2_5") (pintype "passive"))
    )
    (net (code "16") (name "GPIO0") (class "Default")
      (node (ref "J18") (pin "62") (pinfunction "D22_62") (pintype "bidirectional"))
      (node (ref "J3") (pin "48") (pinfunction "48_48") (pintype "passive"))
      (node (ref "JP26") (pin "2") (pinfunction "2_2") (pintype "passive"))
    )
    (net (code "17") (name "GPIO1") (class "Default")
      (node (ref "J18") (pin "64") (pinfunction "D23_64") (pintype "bidirectional"))
      (node (ref "J3") (pin "50") (pinfunction "50_50") (pintype "passive"))
      (node (ref "J6") (pin "7") (pinfunction "REGN_7") (pintype "passive"))
      (node (ref "J6") (pin "@7") (pinfunction "REGN_@7") (pintype "passive"))
      (node (ref "J6") (pin "P$7") (pinfunction "REGN_P$7") (pintype "passive"))
    )
    (net (code "18") (name "LED_BLUE") (class "Default")
      (node (ref "J18") (pin "65") (pinfunction "RGB_BLUE_65") (pintype "bidirectional"))
      (node (ref "J3") (pin "49") (pinfunction "49_49") (pintype "passive"))
      (node (ref "R8") (pin "1") (pinfunction "1_1") (pintype "passive"))
    )
    (net (code "19") (name "LED_GREEN") (class "Default")
      (node (ref "J18") (pin "63") (pinfunction "RGB_GREEN_63") (pintype "bidirectional"))
      (node (ref "J3") (pin "47") (pinfunction "47_47") (pintype "passive"))
      (node (ref "R19") (pin "1") (pinfunction "1_1") (pintype "passive"))
    )
    (net (code "20") (name "LED_RED") (class "Default")
      (node (ref "J18") (pin "61") (pinfunction "RGB_RED_61") (pintype "bidirectional"))
      (node (ref "J3") (pin "45") (pinfunction "45_45") (pintype "passive"))
      (node (ref "R20") (pin "1") (pinfunction "1_1") (pintype "passive"))
    )
    (net (code "21") (name "MISO") (class "Default")
      (node (ref "J18") (pin "50") (pinfunction "MISO_50") (pintype "bidirectional"))
      (node (ref "J3") (pin "36") (pinfunction "36_36") (pintype "passive"))
      (node (ref "JP14") (pin "1") (pinfunction "1_1") (pintype "passive"))
    )
    (net (code "22") (name "MOSI") (class "Default")
      (node (ref "J18") (pin "52") (pinfunction "MOSI_52") (pintype "bidirectional"))
      (node (ref "J3") (pin "38") (pinfunction "38_38") (pintype "passive"))
      (node (ref "JP13") (pin "1") (pinfunction "1_1") (pintype "passive"))
    )
    (net (code "23") (name "NC") (class "Default")
      (node (ref "MS1") (pin "16") (pinfunction "NC_16") (pintype "passive"))
      (node (ref "MS1") (pin "16'") (pinfunction "NC_16'") (pintype "passive"))
    )
    (net (code "24") (name "NFC1") (class "Default")
      (node (ref "J18") (pin "17") (pinfunction "D21_17") (pintype "bidirectional"))
      (node (ref "J3") (pin "11") (pinfunction "11_11") (pintype "passive"))
      (node (ref "NFC") (pin "2@1") (pinfunction "GND_2@1") (pintype "passive"))
      (node (ref "NFC") (pin "2@2") (pinfunction "GND_2@2") (pintype "passive"))
      (node (ref "R37") (pin "1") (pinfunction "1_1") (pintype "bidirectional"))
    )
    (net (code "25") (name "NFC2") (class "Default")
      (node (ref "J18") (pin "19") (pinfunction "D20_19") (pintype "bidirectional"))
      (node (ref "J3") (pin "13") (pinfunction "13_13") (pintype "passive"))
      (node (ref "NFC") (pin "1") (pinfunction "1_1") (pintype "passive"))
      (node (ref "R38") (pin "2") (pinfunction "2_2") (pintype "bidirectional"))
    )
    (net (code "26") (name "Net-(C2-Pad1)") (class "Default")
      (node (ref "C2") (pin "1") (pinfunction "1_1") (pintype "passive"))
      (node (ref "R5") (pin "1") (pinfunction "1_1") (pintype "passive"))
      (node (ref "USB2") (pin "SHLD1") (pinfunction "SHLD_SHLD1") (pintype "bidirectional"))
      (node (ref "USB2") (pin "SHLD2") (pinfunction "SHLD_SHLD2") (pintype "bidirectional"))
      (node (ref "USB2") (pin "SHLD3") (pinfunction "SHLD_SHLD3") (pintype "bidirectional"))
      (node (ref "USB2") (pin "SHLD4") (pinfunction "SHLD_SHLD4") (pintype "bidirectional"))
      (node (ref "USB2") (pin "SHLD5") (pinfunction "SHLD_SHLD5") (pintype "bidirectional"))
      (node (ref "USB2") (pin "SHLD6") (pinfunction "SHLD_SHLD6") (pintype "bidirectional"))
      (node (ref "USB2") (pin "SHLD7") (pinfunction "SHLD_SHLD7") (pintype "bidirectional"))
      (node (ref "USB2") (pin "SHLD8") (pinfunction "SHLD_SHLD8") (pintype "bidirectional"))
    )
    (net (code "27") (name "Net-(C3-Pad1)") (class "Default")
      (node (ref "C3") (pin "1") (pinfunction "1_1") (pintype "passive"))
      (node (ref "R10") (pin "1") (pinfunction "1_1") (pintype "passive"))
      (node (ref "USB1") (pin "SHLD1") (pinfunction "SHLD_SHLD1") (pintype "bidirectional"))
      (node (ref "USB1") (pin "SHLD2") (pinfunction "SHLD_SHLD2") (pintype "bidirectional"))
      (node (ref "USB1") (pin "SHLD3") (pinfunction "SHLD_SHLD3") (pintype "bidirectional"))
      (node (ref "USB1") (pin "SHLD4") (pinfunction "SHLD_SHLD4") (pintype "bidirectional"))
      (node (ref "USB1") (pin "SHLD5") (pinfunction "SHLD_SHLD5") (pintype "bidirectional"))
      (node (ref "USB1") (pin "SHLD6") (pinfunction "SHLD_SHLD6") (pintype "bidirectional"))
      (node (ref "USB1") (pin "SHLD7") (pinfunction "SHLD_SHLD7") (pintype "bidirectional"))
      (node (ref "USB1") (pin "SHLD8") (pinfunction "SHLD_SHLD8") (pintype "bidirectional"))
    )
    (net (code "28") (name "Net-(D2-P$2)") (class "Default")
      (node (ref "D2") (pin "2") (pinfunction "P$2_2") (pintype "bidirectional"))
      (node (ref "JTAG") (pin "1") (pinfunction "1_1") (pintype "bidirectional"))
    )
    (net (code "29") (name "Net-(D4-PadC)") (class "Default")
      (node (ref "D4") (pin "C") (pinfunction "C_C") (pintype "passive"))
      (node (ref "J1") (pin "1") (pinfunction "1_1") (pintype "passive"))
      (node (ref "R23") (pin "2") (pinfunction "2_2") (pintype "passive"))
    )
    (net (code "30") (name "Net-(D17-PadC)") (class "Default")
      (node (ref "D17") (pin "C") (pinfunction "C_C") (pintype "passive"))
      (node (ref "F5") (pin "1") (pinfunction "1_1") (pintype "passive"))
      (node (ref "J2") (pin "1") (pinfunction "1_1") (pintype "passive"))
    )
    (net (code "31") (name "Net-(F5-Pad2)") (class "Default")
      (node (ref "F5") (pin "2") (pinfunction "2_2") (pintype "passive"))
      (node (ref "Q4") (pin "2") (pinfunction "2_2") (pintype "bidirectional"))
      (node (ref "R14") (pin "2") (pinfunction "2_2") (pintype "passive"))
    )
    (net (code "32") (name "Net-(J1-Pad3)") (class "Default")
      (node (ref "J1") (pin "3") (pinfunction "3_3") (pintype "passive"))
      (node (ref "Q5") (pin "3") (pinfunction "3_3") (pintype "bidirectional"))
    )
    (net (code "33") (name "Net-(J3-Pad29)") (class "Default")
      (node (ref "J3") (pin "29") (pinfunction "29_29") (pintype "passive"))
      (node (ref "JP4") (pin "1") (pinfunction "1_1") (pintype "bidirectional"))
    )
    (net (code "34") (name "Net-(J6-5DC-Pad3)") (class "Default")
      (node (ref "J6") (pin "3") (pinfunction "5DC_3") (pintype "passive"))
      (node (ref "J6") (pin "@3") (pinfunction "5DC_@3") (pintype "passive"))
      (node (ref "J6") (pin "P$3") (pinfunction "5DC_P$3") (pintype "passive"))
    )
    (net (code "35") (name "Net-(J6-5DC-Pad4)") (class "Default")
      (node (ref "J6") (pin "4") (pinfunction "5DC_4") (pintype "passive"))
      (node (ref "J6") (pin "@4") (pinfunction "5DC_@4") (pintype "passive"))
      (node (ref "J6") (pin "P$4") (pinfunction "5DC_P$4") (pintype "passive"))
    )
    (net (code "36") (name "Net-(J6-ENABLE-Pad25)") (class "Default")
      (node (ref "J6") (pin "25") (pinfunction "ENABLE_25") (pintype "passive"))
      (node (ref "J6") (pin "@25") (pinfunction "ENABLE_@25") (pintype "passive"))
      (node (ref "J6") (pin "P$25") (pinfunction "ENABLE_P$25") (pintype "passive"))
    )
    (net (code "37") (name "Net-(J6-PG-Pad24)") (class "Default")
      (node (ref "J6") (pin "24") (pinfunction "PG_24") (pintype "passive"))
      (node (ref "J6") (pin "@24") (pinfunction "PG_@24") (pintype "passive"))
      (node (ref "J6") (pin "P$24") (pinfunction "PG_P$24") (pintype "passive"))
      (node (ref "R21") (pin "1") (pinfunction "1_1") (pintype "passive"))
    )
    (net (code "38") (name "Net-(J12-Pad1)") (class "Default")
      (node (ref "J12") (pin "1") (pinfunction "1_1") (pintype "bidirectional"))
      (node (ref "R24") (pin "1") (pinfunction "1_1") (pintype "passive"))
    )
    (net (code "39") (name "Net-(J18-PadSWCLK)") (class "Default")
      (node (ref "J18") (pin "SWCLK") (pinfunction "SWCLK_SWCLK") (pintype "power_in"))
      (node (ref "JTAG") (pin "4") (pinfunction "4_4") (pintype "bidirectional"))
    )
    (net (code "40") (name "Net-(J18-PadSWDIO)") (class "Default")
      (node (ref "J18") (pin "SWDIO") (pinfunction "SWDIO_SWDIO") (pintype "power_in"))
      (node (ref "JTAG") (pin "2") (pinfunction "2_2") (pintype "bidirectional"))
    )
    (net (code "41") (name "Net-(J18-PadSWO)") (class "Default")
      (node (ref "J18") (pin "SWO") (pinfunction "SWO_SWO") (pintype "power_in"))
      (node (ref "JTAG") (pin "6") (pinfunction "6_6") (pintype "bidirectional"))
    )
    (net (code "42") (name "Net-(J19-Pad1)") (class "Default")
      (node (ref "J19") (pin "1") (pinfunction "1_1") (pintype "bidirectional"))
      (node (ref "R25") (pin "1") (pinfunction "1_1") (pintype "passive"))
    )
    (net (code "43") (name "Net-(J20-Pad1)") (class "Default")
      (node (ref "J20") (pin "1") (pinfunction "1_1") (pintype "bidirectional"))
      (node (ref "R26") (pin "1") (pinfunction "1_1") (pintype "passive"))
    )
    (net (code "44") (name "Net-(J21-Pad2)") (class "Default")
      (node (ref "J21") (pin "2") (pinfunction "2_2") (pintype "bidirectional"))
      (node (ref "RT1") (pin "1") (pinfunction "1_1") (pintype "bidirectional"))
      (node (ref "RT2") (pin "2") (pinfunction "2_2") (pintype "bidirectional"))
      (node (ref "TP2") (pin "1") (pinfunction "1_1") (pintype "bidirectional"))
      (node (ref "TP5") (pin "1") (pinfunction "1_1") (pintype "bidirectional"))
    )
    (net (code "45") (name "Net-(JP1-Pad1)") (class "Default")
      (node (ref "JP1") (pin "1") (pinfunction "1_1") (pintype "bidirectional"))
      (node (ref "R27") (pin "1") (pinfunction "1_1") (pintype "passive"))
    )
    (net (code "46") (name "Net-(JP2-Pad1)") (class "Default")
      (node (ref "JP2") (pin "1") (pinfunction "1_1") (pintype "bidirectional"))
      (node (ref "R28") (pin "1") (pinfunction "1_1") (pintype "passive"))
    )
    (net (code "47") (name "Net-(JP3-Pad1)") (class "Default")
      (node (ref "JP3") (pin "1") (pinfunction "1_1") (pintype "bidirectional"))
      (node (ref "R29") (pin "1") (pinfunction "1_1") (pintype "passive"))
    )
    (net (code "48") (name "Net-(JP5-Pad2)") (class "Default")
      (node (ref "JP5") (pin "2") (pinfunction "2_2") (pintype "passive"))
      (node (ref "MS1") (pin "1") (pinfunction "~{RST}_1") (pintype "input"))
      (node (ref "MS1") (pin "1'") (pinfunction "~{RST}_1'") (pintype "input"))
    )
    (net (code "49") (name "Net-(JP6-Pad2)") (class "Default")
      (node (ref "JP6") (pin "2") (pinfunction "2_2") (pintype "passive"))
      (node (ref "MS1") (pin "5") (pinfunction "A0_5") (pintype "bidirectional"))
      (node (ref "MS1") (pin "5'") (pinfunction "A0_5'") (pintype "bidirectional"))
    )
    (net (code "50") (name "Net-(JP7-Pad2)") (class "Default")
      (node (ref "JP7") (pin "2") (pinfunction "2_2") (pintype "passive"))
      (node (ref "MS1") (pin "6") (pinfunction "A1_6") (pintype "bidirectional"))
      (node (ref "MS1") (pin "6'") (pinfunction "A1_6'") (pintype "bidirectional"))
    )
    (net (code "51") (name "Net-(JP8-Pad2)") (class "Default")
      (node (ref "JP8") (pin "2") (pinfunction "2_2") (pintype "passive"))
      (node (ref "MS1") (pin "7") (pinfunction "A2_7") (pintype "bidirectional"))
      (node (ref "MS1") (pin "7'") (pinfunction "A2_7'") (pintype "bidirectional"))
    )
    (net (code "52") (name "Net-(JP9-Pad2)") (class "Default")
      (node (ref "JP9") (pin "2") (pinfunction "2_2") (pintype "passive"))
      (node (ref "MS1") (pin "8") (pinfunction "A3_8") (pintype "bidirectional"))
      (node (ref "MS1") (pin "8'") (pinfunction "A3_8'") (pintype "bidirectional"))
    )
    (net (code "53") (name "Net-(JP10-Pad2)") (class "Default")
      (node (ref "JP10") (pin "2") (pinfunction "2_2") (pintype "passive"))
      (node (ref "MS1") (pin "9") (pinfunction "A4_9") (pintype "bidirectional"))
      (node (ref "MS1") (pin "9'") (pinfunction "A4_9'") (pintype "bidirectional"))
    )
    (net (code "54") (name "Net-(JP11-Pad2)") (class "Default")
      (node (ref "JP11") (pin "2") (pinfunction "2_2") (pintype "passive"))
      (node (ref "MS1") (pin "10") (pinfunction "A5_10") (pintype "bidirectional"))
      (node (ref "MS1") (pin "10'") (pinfunction "A5_10'") (pintype "bidirectional"))
    )
    (net (code "55") (name "Net-(JP12-Pad2)") (class "Default")
      (node (ref "JP12") (pin "2") (pinfunction "2_2") (pintype "passive"))
      (node (ref "MS1") (pin "11") (pinfunction "SCK_11") (pintype "bidirectional"))
      (node (ref "MS1") (pin "11'") (pinfunction "SCK_11'") (pintype "bidirectional"))
    )
    (net (code "56") (name "Net-(JP13-Pad2)") (class "Default")
      (node (ref "JP13") (pin "2") (pinfunction "2_2") (pintype "passive"))
      (node (ref "MS1") (pin "12") (pinfunction "MOSI_12") (pintype "bidirectional"))
      (node (ref "MS1") (pin "12'") (pinfunction "MOSI_12'") (pintype "bidirectional"))
    )
    (net (code "57") (name "Net-(JP14-Pad2)") (class "Default")
      (node (ref "JP14") (pin "2") (pinfunction "2_2") (pintype "passive"))
      (node (ref "MS1") (pin "13") (pinfunction "MISO_13") (pintype "bidirectional"))
      (node (ref "MS1") (pin "13'") (pinfunction "MISO_13'") (pintype "bidirectional"))
    )
    (net (code "58") (name "Net-(JP15-Pad2)") (class "Default")
      (node (ref "JP15") (pin "2") (pinfunction "2_2") (pintype "passive"))
      (node (ref "MS1") (pin "14") (pinfunction "RX_14") (pintype "bidirectional"))
      (node (ref "MS1") (pin "14'") (pinfunction "RX_14'") (pintype "bidirectional"))
    )
    (net (code "59") (name "Net-(JP16-Pad2)") (class "Default")
      (node (ref "JP16") (pin "2") (pinfunction "2_2") (pintype "passive"))
      (node (ref "MS1") (pin "15") (pinfunction "TX_15") (pintype "bidirectional"))
      (node (ref "MS1") (pin "15'") (pinfunction "TX_15'") (pintype "bidirectional"))
    )
    (net (code "60") (name "Net-(JP17-Pad1)") (class "Default")
      (node (ref "JP17") (pin "1") (pinfunction "1_1") (pintype "passive"))
      (node (ref "MS1") (pin "28") (pinfunction "LI+_28") (pintype "power_in"))
      (node (ref "MS1") (pin "28'") (pinfunction "LI+_28'") (pintype "power_in"))
    )
    (net (code "61") (name "Net-(JP19-Pad1)") (class "Default")
      (node (ref "JP19") (pin "1") (pinfunction "1_1") (pintype "passive"))
      (node (ref "MS1") (pin "26") (pinfunction "VUSB_26") (pintype "power_in"))
      (node (ref "MS1") (pin "26'") (pinfunction "VUSB_26'") (pintype "power_in"))
    )
    (net (code "62") (name "Net-(JP20-Pad1)") (class "Default")
      (node (ref "JP20") (pin "1") (pinfunction "1_1") (pintype "passive"))
      (node (ref "MS1") (pin "25") (pinfunction "D8_25") (pintype "bidirectional"))
      (node (ref "MS1") (pin "25'") (pinfunction "D8_25'") (pintype "bidirectional"))
    )
    (net (code "63") (name "Net-(JP21-Pad1)") (class "Default")
      (node (ref "JP21") (pin "1") (pinfunction "1_1") (pintype "passive"))
      (node (ref "MS1") (pin "24") (pinfunction "D7_24") (pintype "bidirectional"))
      (node (ref "MS1") (pin "24'") (pinfunction "D7_24'") (pintype "bidirectional"))
    )
    (net (code "64") (name "Net-(JP22-Pad1)") (class "Default")
      (node (ref "JP22") (pin "1") (pinfunction "1_1") (pintype "passive"))
      (node (ref "MS1") (pin "23") (pinfunction "D6_23") (pintype "bidirectional"))
      (node (ref "MS1") (pin "23'") (pinfunction "D6_23'") (pintype "bidirectional"))
    )
    (net (code "65") (name "Net-(JP23-Pad1)") (class "Default")
      (node (ref "JP23") (pin "1") (pinfunction "1_1") (pintype "passive"))
      (node (ref "MS1") (pin "22") (pinfunction "D5_22") (pintype "bidirectional"))
      (node (ref "MS1") (pin "22'") (pinfunction "D5_22'") (pintype "bidirectional"))
    )
    (net (code "66") (name "Net-(JP24-Pad1)") (class "Default")
      (node (ref "JP24") (pin "1") (pinfunction "1_1") (pintype "passive"))
      (node (ref "MS1") (pin "21") (pinfunction "D4_21") (pintype "bidirectional"))
      (node (ref "MS1") (pin "21'") (pinfunction "D4_21'") (pintype "bidirectional"))
    )
    (net (code "67") (name "Net-(JP25-Pad1)") (class "Default")
      (node (ref "JP25") (pin "1") (pinfunction "1_1") (pintype "passive"))
      (node (ref "MS1") (pin "20") (pinfunction "D3_20") (pintype "bidirectional"))
      (node (ref "MS1") (pin "20'") (pinfunction "D3_20'") (pintype "bidirectional"))
    )
    (net (code "68") (name "Net-(JP26-Pad1)") (class "Default")
      (node (ref "JP26") (pin "1") (pinfunction "1_1") (pintype "passive"))
      (node (ref "MS1") (pin "19") (pinfunction "D2_19") (pintype "bidirectional"))
      (node (ref "MS1") (pin "19'") (pinfunction "D2_19'") (pintype "bidirectional"))
    )
    (net (code "69") (name "Net-(JP27-Pad1)") (class "Default")
      (node (ref "JP27") (pin "1") (pinfunction "1_1") (pintype "passive"))
      (node (ref "MS1") (pin "18") (pinfunction "SCL_18") (pintype "bidirectional"))
      (node (ref "MS1") (pin "18'") (pinfunction "SCL_18'") (pintype "bidirectional"))
    )
    (net (code "70") (name "Net-(JP28-Pad1)") (class "Default")
      (node (ref "JP28") (pin "1") (pinfunction "1_1") (pintype "passive"))
      (node (ref "MS1") (pin "17") (pinfunction "SDA_17") (pintype "bidirectional"))
      (node (ref "MS1") (pin "17'") (pinfunction "SDA_17'") (pintype "bidirectional"))
    )
    (net (code "71") (name "Net-(LED1-A)") (class "Default")
      (node (ref "LED1") (pin "1") (pinfunction "A_1") (pintype "bidirectional"))
      (node (ref "R16") (pin "2") (pinfunction "2_2") (pintype "passive"))
      (node (ref "R18") (pin "1") (pinfunction "1_1") (pintype "passive"))
    )
    (net (code "72") (name "Net-(LED1-K)") (class "Default")
      (node (ref "LED1") (pin "2") (pinfunction "K_2") (pintype "bidirectional"))
      (node (ref "Q1") (pin "3") (pinfunction "3_3") (pintype "bidirectional"))
      (node (ref "R22") (pin "2") (pinfunction "2_2") (pintype "passive"))
    )
    (net (code "73") (name "Net-(LED3-K)") (class "Default")
      (node (ref "LED3") (pin "2") (pinfunction "K_2") (pintype "bidirectional"))
      (node (ref "R13") (pin "1") (pinfunction "1_1") (pintype "bidirectional"))
    )
    (net (code "74") (name "Net-(MS1-MD-Pad3')") (class "Default")
      (node (ref "MS1") (pin "3") (pinfunction "MD_3") (pintype "bidirectional"))
      (node (ref "MS1") (pin "3'") (pinfunction "MD_3'") (pintype "bidirectional"))
    )
    (net (code "75") (name "Net-(Q1-Pad1)") (class "Default")
      (node (ref "Q1") (pin "1") (pinfunction "1_1") (pintype "bidirectional"))
      (node (ref "R11") (pin "1") (pinfunction "1_1") (pintype "passive"))
      (node (ref "R17") (pin "2") (pinfunction "2_2") (pintype "passive"))
    )
    (net (code "76") (name "Net-(Q3-Pad1)") (class "Default")
      (node (ref "Q3") (pin "1") (pinfunction "1_1") (pintype "bidirectional"))
      (node (ref "Q5") (pin "1") (pinfunction "1_1") (pintype "bidirectional"))
      (node (ref "R30") (pin "1") (pinfunction "1_1") (pintype "bidirectional"))
      (node (ref "R31") (pin "1") (pinfunction "1_1") (pintype "bidirectional"))
    )
    (net (code "77") (name "Net-(Q3-Pad2)") (class "Default")
      (node (ref "Q3") (pin "2") (pinfunction "2_2") (pintype "bidirectional"))
      (node (ref "Q5") (pin "2") (pinfunction "2_2") (pintype "bidirectional"))
      (node (ref "R30") (pin "2") (pinfunction "2_2") (pintype "bidirectional"))
      (node (ref "R33") (pin "2") (pinfunction "2_2") (pintype "bidirectional"))
    )
    (net (code "78") (name "Net-(Q4-Pad1)") (class "Default")
      (node (ref "Q4") (pin "1") (pinfunction "1_1") (pintype "bidirectional"))
      (node (ref "R14") (pin "1") (pinfunction "1_1") (pintype "passive"))
      (node (ref "R15") (pin "2") (pinfunction "2_2") (pintype "passive"))
    )
    (net (code "79") (name "Net-(R15-Pad1)") (class "Default")
      (node (ref "R15") (pin "1") (pinfunction "1_1") (pintype "passive"))
      (node (ref "S1") (pin "3") (pinfunction "3_3") (pintype "bidirectional"))
      (node (ref "S1") (pin "6") (pinfunction "6_6") (pintype "bidirectional"))
    )
    (net (code "80") (name "Net-(R31-Pad2)") (class "Default")
      (node (ref "R31") (pin "2") (pinfunction "2_2") (pintype "bidirectional"))
      (node (ref "S4") (pin "2") (pinfunction "2_2") (pintype "bidirectional"))
      (node (ref "S4") (pin "5") (pinfunction "5_5") (pintype "bidirectional"))
    )
    (net (code "81") (name "Net-(R33-Pad1)") (class "Default")
      (node (ref "R33") (pin "1") (pinfunction "1_1") (pintype "bidirectional"))
      (node (ref "S4") (pin "1") (pinfunction "1_1") (pintype "bidirectional"))
      (node (ref "S4") (pin "4") (pinfunction "4_4") (pintype "bidirectional"))
    )
    (net (code "82") (name "Net-(RGB-2)") (class "Default")
      (node (ref "R8") (pin "2") (pinfunction "2_2") (pintype "passive"))
      (node (ref "RGB") (pin "BLUE") (pinfunction "2_BLUE") (pintype "passive"))
    )
    (net (code "83") (name "Net-(RGB-3)") (class "Default")
      (node (ref "R19") (pin "2") (pinfunction "2_2") (pintype "passive"))
      (node (ref "RGB") (pin "GREEN") (pinfunction "3_GREEN") (pintype "passive"))
    )
    (net (code "84") (name "Net-(RGB-4)") (class "Default")
      (node (ref "R20") (pin "2") (pinfunction "2_2") (pintype "passive"))
      (node (ref "RGB") (pin "RED") (pinfunction "4_RED") (pintype "passive"))
    )
    (net (code "85") (name "Net-(S1-Pad1)") (class "Default")
      (node (ref "S1") (pin "1") (pinfunction "1_1") (pintype "bidirectional"))
      (node (ref "S1") (pin "4") (pinfunction "4_4") (pintype "bidirectional"))
    )
    (net (code "86") (name "Net-(U1-CE)") (class "Default")
      (node (ref "R2") (pin "1") (pinfunction "1_1") (pintype "passive"))
      (node (ref "R7") (pin "1") (pinfunction "1_1") (pintype "passive"))
      (node (ref "U1") (pin "4") (pinfunction "CE_4") (pintype "bidirectional"))
    )
    (net (code "87") (name "Net-(U2-A0)") (class "Default")
      (node (ref "J20") (pin "2") (pinfunction "2_2") (pintype "bidirectional"))
      (node (ref "JP3") (pin "2") (pinfunction "2_2") (pintype "bidirectional"))
      (node (ref "U2") (pin "1") (pinfunction "A0_1") (pintype "input"))
    )
    (net (code "88") (name "Net-(U2-A1)") (class "Default")
      (node (ref "J19") (pin "2") (pinfunction "2_2") (pintype "bidirectional"))
      (node (ref "JP2") (pin "2") (pinfunction "2_2") (pintype "bidirectional"))
      (node (ref "U2") (pin "2") (pinfunction "A1_2") (pintype "input"))
    )
    (net (code "89") (name "Net-(U2-A2)") (class "Default")
      (node (ref "J12") (pin "2") (pinfunction "2_2") (pintype "bidirectional"))
      (node (ref "JP1") (pin "2") (pinfunction "2_2") (pintype "bidirectional"))
      (node (ref "U2") (pin "3") (pinfunction "A2_3") (pintype "input"))
    )
    (net (code "90") (name "Net-(USB1-CC1)") (class "Default")
      (node (ref "R6") (pin "1") (pinfunction "1_1") (pintype "passive"))
      (node (ref "USB1") (pin "A5") (pinfunction "CC1_A5") (pintype "bidirectional"))
    )
    (net (code "91") (name "Net-(USB1-CC2)") (class "Default")
      (node (ref "R9") (pin "1") (pinfunction "1_1") (pintype "passive"))
      (node (ref "USB1") (pin "B5") (pinfunction "CC2_B5") (pintype "bidirectional"))
    )
    (net (code "92") (name "Net-(USB2-CC1)") (class "Default")
      (node (ref "R1") (pin "1") (pinfunction "1_1") (pintype "passive"))
      (node (ref "USB2") (pin "A5") (pinfunction "CC1_A5") (pintype "bidirectional"))
    )
    (net (code "93") (name "Net-(USB2-CC2)") (class "Default")
      (node (ref "R3") (pin "1") (pinfunction "1_1") (pintype "passive"))
      (node (ref "USB2") (pin "B5") (pinfunction "CC2_B5") (pintype "bidirectional"))
    )
    (net (code "94") (name "PWM0") (class "Default")
      (node (ref "J18") (pin "66") (pinfunction "D4_66") (pintype "bidirectional"))
      (node (ref "J3") (pin "52") (pinfunction "52_52") (pintype "passive"))
      (node (ref "JP24") (pin "2") (pinfunction "2_2") (pintype "passive"))
    )
    (net (code "95") (name "PWM1") (class "Default")
      (node (ref "J18") (pin "68") (pinfunction "D5_68") (pintype "bidirectional"))
      (node (ref "J3") (pin "54") (pinfunction "54_54") (pintype "passive"))
      (node (ref "JP20") (pin "2") (pinfunction "2_2") (pintype "passive"))
    )
    (net (code "96") (name "PWM2") (class "Default")
      (node (ref "J18") (pin "70") (pinfunction "D6_70") (pintype "bidirectional"))
      (node (ref "J3") (pin "56") (pinfunction "56_56") (pintype "passive"))
      (node (ref "JP22") (pin "2") (pinfunction "2_2") (pintype "passive"))
    )
    (net (code "97") (name "PWM3") (class "Default")
      (node (ref "J18") (pin "72") (pinfunction "D7_72") (pintype "bidirectional"))
      (node (ref "J3") (pin "58") (pinfunction "58_58") (pintype "passive"))
      (node (ref "JP21") (pin "2") (pinfunction "2_2") (pintype "passive"))
    )
    (net (code "98") (name "REGN") (class "Default")
      (node (ref "J6") (pin "8") (pinfunction "NC_8") (pintype "passive"))
      (node (ref "J6") (pin "@8") (pinfunction "NC_@8") (pintype "passive"))
      (node (ref "J6") (pin "P$8") (pinfunction "NC_P$8") (pintype "passive"))
      (node (ref "RT1") (pin "2") (pinfunction "2_2") (pintype "bidirectional"))
      (node (ref "TP1") (pin "1") (pinfunction "1_1") (pintype "bidirectional"))
    )
    (net (code "99") (name "RTS") (class "Default")
      (node (ref "J18") (pin "42") (pinfunction "RTS_42") (pintype "bidirectional"))
      (node (ref "J3") (pin "28") (pinfunction "28_28") (pintype "passive"))
    )
    (net (code "100") (name "RX") (class "Default")
      (node (ref "J18") (pin "38") (pinfunction "RXD_38") (pintype "bidirectional"))
      (node (ref "J3") (pin "24") (pinfunction "24_24") (pintype "passive"))
      (node (ref "JP15") (pin "1") (pinfunction "1_1") (pintype "passive"))
    )
    (net (code "101") (name "SCK") (class "Default")
      (node (ref "J18") (pin "54") (pinfunction "SCLK_54") (pintype "bidirectional"))
      (node (ref "J3") (pin "40") (pinfunction "40_40") (pintype "passive"))
      (node (ref "JP12") (pin "1") (pinfunction "1_1") (pintype "passive"))
    )
    (net (code "102") (name "SCL") (class "Default")
      (node (ref "J18") (pin "20") (pinfunction "SCL_20") (pintype "bidirectional"))
      (node (ref "J3") (pin "14") (pinfunction "14_14") (pintype "passive"))
      (node (ref "J4") (pin "4") (pinfunction "4_4") (pintype "passive"))
      (node (ref "J6") (pin "14") (pinfunction "SCL_14") (pintype "passive"))
      (node (ref "J6") (pin "@14") (pinfunction "SCL_@14") (pintype "passive"))
      (node (ref "J6") (pin "P$14") (pinfunction "SCL_P$14") (pintype "passive"))
      (node (ref "JP27") (pin "2") (pinfunction "2_2") (pintype "passive"))
      (node (ref "U2") (pin "6") (pinfunction "SCL_6") (pintype "input"))
    )
    (net (code "103") (name "SDA") (class "Default")
      (node (ref "J18") (pin "22") (pinfunction "SDA_22") (pintype "bidirectional"))
      (node (ref "J3") (pin "16") (pinfunction "16_16") (pintype "passive"))
      (node (ref "J4") (pin "3") (pinfunction "3_3") (pintype "passive"))
      (node (ref "J6") (pin "15") (pinfunction "SDA_15") (pintype "passive"))
      (node (ref "J6") (pin "@15") (pinfunction "SDA_@15") (pintype "passive"))
      (node (ref "J6") (pin "P$15") (pinfunction "SDA_P$15") (pintype "passive"))
      (node (ref "JP28") (pin "2") (pinfunction "2_2") (pintype "passive"))
      (node (ref "U2") (pin "5") (pinfunction "SDA_5") (pintype "bidirectional"))
    )
    (net (code "104") (name "SOM5") (class "Default")
      (node (ref "C7") (pin "1") (pinfunction "1_1") (pintype "passive"))
      (node (ref "D7") (pin "2") (pinfunction "2_2") (pintype "bidirectional"))
      (node (ref "J13") (pin "C1") (pinfunction "VCC_C1") (pintype "passive"))
      (node (ref "J18") (pin "67") (pinfunction "SIM_VCC_67") (pintype "power_in"))
      (node (ref "J3") (pin "51") (pinfunction "51_51") (pintype "passive"))
      (node (ref "U7") (pin "8") (pinfunction "VCC_8") (pintype "power_in"))
    )
    (net (code "105") (name "SOM6") (class "Default")
      (node (ref "C4") (pin "1") (pinfunction "1_1") (pintype "passive"))
      (node (ref "D13") (pin "2") (pinfunction "2_2") (pintype "bidirectional"))
      (node (ref "J13") (pin "C2") (pinfunction "RST_C2") (pintype "passive"))
      (node (ref "J18") (pin "69") (pinfunction "SIM_RST_69") (pintype "bidirectional"))
      (node (ref "J3") (pin "53") (pinfunction "53_53") (pintype "passive"))
      (node (ref "U7") (pin "7") (pinfunction "RST_7") (pintype "bidirectional"))
    )
    (net (code "106") (name "SOM7") (class "Default")
      (node (ref "C6") (pin "1") (pinfunction "1_1") (pintype "passive"))
      (node (ref "D11") (pin "2") (pinfunction "2_2") (pintype "bidirectional"))
      (node (ref "J13") (pin "C3") (pinfunction "CLK_C3") (pintype "passive"))
      (node (ref "J18") (pin "71") (pinfunction "SIM_CLK_71") (pintype "bidirectional"))
      (node (ref "J3") (pin "55") (pinfunction "55_55") (pintype "passive"))
      (node (ref "U7") (pin "6") (pinfunction "CLK_6") (pintype "bidirectional"))
    )
    (net (code "107") (name "SOM8") (class "Default")
      (node (ref "C5") (pin "1") (pinfunction "1_1") (pintype "passive"))
      (node (ref "D12") (pin "2") (pinfunction "2_2") (pintype "bidirectional"))
      (node (ref "J13") (pin "C7") (pinfunction "I/O_C7") (pintype "passive"))
      (node (ref "J18") (pin "73") (pinfunction "SIM_DATA_73") (pintype "bidirectional"))
      (node (ref "J3") (pin "57") (pinfunction "57_57") (pintype "passive"))
      (node (ref "U7") (pin "3") (pinfunction "IO_3") (pintype "bidirectional"))
    )
    (net (code "108") (name "SOM9") (class "Default")
      (node (ref "J18") (pin "75") (pinfunction "NC_75") (pintype "bidirectional"))
      (node (ref "J3") (pin "60") (pinfunction "60_60") (pintype "passive"))
    )
    (net (code "109") (name "SOM10") (class "Default")
      (node (ref "J18") (pin "14") (pinfunction "NC_14") (pintype "bidirectional"))
      (node (ref "J3") (pin "10") (pinfunction "10_10") (pintype "passive"))
    )
    (net (code "110") (name "SOM11") (class "Default")
      (node (ref "J18") (pin "18") (pinfunction "GNSS_TXD_18") (pintype "bidirectional"))
      (node (ref "J3") (pin "12") (pinfunction "12_12") (pintype "passive"))
    )
    (net (code "111") (name "SOM12") (class "Default")
      (node (ref "J18") (pin "58") (pinfunction "D24_58") (pintype "bidirectional"))
      (node (ref "J3") (pin "44") (pinfunction "44_44") (pintype "passive"))
    )
    (net (code "112") (name "SOM13") (class "Default")
      (node (ref "J18") (pin "60") (pinfunction "D25_60") (pintype "bidirectional"))
      (node (ref "J3") (pin "46") (pinfunction "46_46") (pintype "passive"))
    )
    (net (code "113") (name "SOM14") (class "Default")
      (node (ref "J18") (pin "51") (pinfunction "NC_51") (pintype "bidirectional"))
      (node (ref "J3") (pin "35") (pinfunction "35_35") (pintype "passive"))
    )
    (net (code "114") (name "SOM15") (class "Default")
      (node (ref "J18") (pin "53") (pinfunction "SWD_CLK_53") (pintype "bidirectional"))
      (node (ref "J3") (pin "37") (pinfunction "37_37") (pintype "passive"))
    )
    (net (code "115") (name "SOM16") (class "Default")
      (node (ref "J18") (pin "55") (pinfunction "SWD_DATA_55") (pintype "bidirectional"))
      (node (ref "J3") (pin "39") (pinfunction "39_39") (pintype "passive"))
    )
    (net (code "116") (name "SOM17") (class "Default")
      (node (ref "J18") (pin "57") (pinfunction "D27_57") (pintype "bidirectional"))
      (node (ref "J3") (pin "41") (pinfunction "41_41") (pintype "bidirectional"))
    )
    (net (code "117") (name "SOM18") (class "Default")
      (node (ref "J18") (pin "59") (pinfunction "D26_59") (pintype "bidirectional"))
      (node (ref "J3") (pin "43") (pinfunction "43_43") (pintype "passive"))
    )
    (net (code "118") (name "TS") (class "Default")
      (node (ref "J21") (pin "1") (pinfunction "1_1") (pintype "bidirectional"))
      (node (ref "J6") (pin "17") (pinfunction "TS_17") (pintype "passive"))
      (node (ref "J6") (pin "@17") (pinfunction "TS_@17") (pintype "passive"))
      (node (ref "J6") (pin "P$17") (pinfunction "TS_P$17") (pintype "passive"))
      (node (ref "R23") (pin "1") (pinfunction "1_1") (pintype "passive"))
    )
    (net (code "119") (name "TX") (class "Default")
      (node (ref "J18") (pin "36") (pinfunction "TXD_36") (pintype "bidirectional"))
      (node (ref "J3") (pin "22") (pinfunction "22_22") (pintype "passive"))
      (node (ref "JP16") (pin "1") (pinfunction "1_1") (pintype "passive"))
    )
    (net (code "120") (name "UB_USB_N") (class "Default")
      (node (ref "D23") (pin "1") (pinfunction "1_1") (pintype "bidirectional"))
      (node (ref "J18") (pin "46") (pinfunction "UB_USB_N_46") (pintype "bidirectional"))
      (node (ref "USB2") (pin "A7") (pinfunction "D-_A7") (pintype "bidirectional"))
      (node (ref "USB2") (pin "B7") (pinfunction "D-_B7") (pintype "bidirectional"))
    )
    (net (code "121") (name "UB_USB_P") (class "Default")
      (node (ref "D23") (pin "4") (pinfunction "4_4") (pintype "bidirectional"))
      (node (ref "J18") (pin "44") (pinfunction "UB_USB_P_44") (pintype "bidirectional"))
      (node (ref "USB2") (pin "A6") (pinfunction "D+_A6") (pintype "bidirectional"))
      (node (ref "USB2") (pin "B6") (pinfunction "D+_B6") (pintype "bidirectional"))
    )
    (net (code "122") (name "UB_VBUS") (class "Default")
      (node (ref "D23") (pin "5") (pinfunction "5_5") (pintype "bidirectional"))
      (node (ref "F4") (pin "P$2") (pinfunction "2_P$2") (pintype "bidirectional"))
      (node (ref "USB2") (pin "VBUS1") (pinfunction "VBUS_VBUS1") (pintype "bidirectional"))
      (node (ref "USB2") (pin "VBUS2") (pinfunction "VBUS_VBUS2") (pintype "bidirectional"))
    )
    (net (code "123") (name "UB_VBUS1") (class "Default")
      (node (ref "F4") (pin "P$1") (pinfunction "1_P$1") (pintype "bidirectional"))
      (node (ref "J18") (pin "74") (pinfunction "MODEM_VBUS_74") (pintype "power_in"))
    )
    (net (code "124") (name "USB_N") (class "Default")
      (node (ref "D1") (pin "1") (pinfunction "1_1") (pintype "bidirectional"))
      (node (ref "J18") (pin "13") (pinfunction "USB_N_13") (pintype "bidirectional"))
      (node (ref "USB1") (pin "A7") (pinfunction "D-_A7") (pintype "bidirectional"))
      (node (ref "USB1") (pin "B7") (pinfunction "D-_B7") (pintype "bidirectional"))
    )
    (net (code "125") (name "USB_P") (class "Default")
      (node (ref "D1") (pin "4") (pinfunction "4_4") (pintype "bidirectional"))
      (node (ref "J18") (pin "11") (pinfunction "USB_P_11") (pintype "bidirectional"))
      (node (ref "USB1") (pin "A6") (pinfunction "D+_A6") (pintype "bidirectional"))
      (node (ref "USB1") (pin "B6") (pinfunction "D+_B6") (pintype "bidirectional"))
    )
    (net (code "126") (name "VBAT") (class "Default")
      (node (ref "J6") (pin "18") (pinfunction "VBAT_18") (pintype "passive"))
      (node (ref "J6") (pin "19") (pinfunction "VBAT_19") (pintype "passive"))
      (node (ref "J6") (pin "20") (pinfunction "VBAT_20") (pintype "passive"))
      (node (ref "J6") (pin "@18") (pinfunction "VBAT_@18") (pintype "passive"))
      (node (ref "J6") (pin "@19") (pinfunction "VBAT_@19") (pintype "passive"))
      (node (ref "J6") (pin "@20") (pinfunction "VBAT_@20") (pintype "passive"))
      (node (ref "J6") (pin "P$18") (pinfunction "VBAT_P$18") (pintype "passive"))
      (node (ref "J6") (pin "P$19") (pinfunction "VBAT_P$19") (pintype "passive"))
      (node (ref "J6") (pin "P$20") (pinfunction "VBAT_P$20") (pintype "passive"))
      (node (ref "JP17") (pin "2") (pinfunction "2_2") (pintype "passive"))
      (node (ref "Q3") (pin "3") (pinfunction "3_3") (pintype "bidirectional"))
      (node (ref "VBAT") (pin "1") (pinfunction "TP_1") (pintype "bidirectional"))
    )
    (net (code "127") (name "VBUS") (class "Default")
      (node (ref "F2") (pin "P$2") (pinfunction "2_P$2") (pintype "bidirectional"))
      (node (ref "U1") (pin "5") (pinfunction "VIN_5") (pintype "power_in"))
    )
    (net (code "128") (name "VCC") (class "Default")
      (node (ref "C10") (pin "1") (pinfunction "1_1") (pintype "passive"))
      (node (ref "C20") (pin "1") (pinfunction "1_1") (pintype "passive"))
      (node (ref "C61") (pin "1") (pinfunction "1_1") (pintype "passive"))
      (node (ref "C8") (pin "1") (pinfunction "1_1") (pintype "passive"))
      (node (ref "C9") (pin "1") (pinfunction "1_1") (pintype "passive"))
      (node (ref "D16") (pin "2") (pinfunction "P$2_2") (pintype "bidirectional"))
      (node (ref "J18") (pin "2") (pinfunction "VCC_2") (pintype "power_in"))
      (node (ref "J18") (pin "4") (pinfunction "VCC_4") (pintype "power_in"))
      (node (ref "J18") (pin "6") (pinfunction "VCC_6") (pintype "power_in"))
      (node (ref "J18") (pin "8") (pinfunction "VCC_8") (pintype "power_in"))
      (node (ref "J3") (pin "2") (pinfunction "2_2") (pintype "passive"))
      (node (ref "J3") (pin "4") (pinfunction "4_4") (pintype "passive"))
      (node (ref "J3") (pin "6") (pinfunction "6_6") (pintype "passive"))
      (node (ref "J6") (pin "5") (pinfunction "VCC_5") (pintype "passive"))
      (node (ref "J6") (pin "6") (pinfunction "VCC_6") (pintype "passive"))
      (node (ref "J6") (pin "@5") (pinfunction "VCC_@5") (pintype "passive"))
      (node (ref "J6") (pin "@6") (pinfunction "VCC_@6") (pintype "passive"))
      (node (ref "J6") (pin "P$5") (pinfunction "VCC_P$5") (pintype "passive"))
      (node (ref "J6") (pin "P$6") (pinfunction "VCC_P$6") (pintype "passive"))
      (node (ref "VCC") (pin "1") (pinfunction "TP_1") (pintype "bidirectional"))
    )
    (net (code "129") (name "VIN") (class "Default")
      (node (ref "J6") (pin "11") (pinfunction "VIN_11") (pintype "passive"))
      (node (ref "J6") (pin "12") (pinfunction "VIN_12") (pintype "passive"))
      (node (ref "J6") (pin "@11") (pinfunction "VIN_@11") (pintype "passive"))
      (node (ref "J6") (pin "@12") (pinfunction "VIN_@12") (pintype "passive"))
      (node (ref "J6") (pin "P$11") (pinfunction "VIN_P$11") (pintype "passive"))
      (node (ref "J6") (pin "P$12") (pinfunction "VIN_P$12") (pintype "passive"))
      (node (ref "Q4") (pin "3") (pinfunction "3_3") (pintype "bidirectional"))
      (node (ref "R11") (pin "2") (pinfunction "2_2") (pintype "passive"))
      (node (ref "R18") (pin "2") (pinfunction "2_2") (pintype "passive"))
      (node (ref "VIN") (pin "1") (pinfunction "TP_1") (pintype "bidirectional"))
    )
    (net (code "130") (name "VPP") (class "Default")
      (node (ref "U7") (pin "2") (pinfunction "VPP_2") (pintype "power_in"))
    )
    (net (code "131") (name "VUSB") (class "Default")
      (node (ref "D1") (pin "5") (pinfunction "5_5") (pintype "bidirectional"))
      (node (ref "F2") (pin "P$1") (pinfunction "1_P$1") (pintype "bidirectional"))
      (node (ref "USB1") (pin "VBUS1") (pinfunction "VBUS_VBUS1") (pintype "bidirectional"))
      (node (ref "USB1") (pin "VBUS2") (pinfunction "VBUS_VBUS2") (pintype "bidirectional"))
    )
    (net (code "132") (name "VUSB-MCU") (class "Default")
      (node (ref "J18") (pin "16") (pinfunction "NC_16") (pintype "power_in"))
      (node (ref "JP19") (pin "2") (pinfunction "2_2") (pintype "passive"))
      (node (ref "U1") (pin "1") (pinfunction "VOUT_1") (pintype "power_in"))
    )
    (net (code "133") (name "unconnected-(D1-Pad3)") (class "Default")
      (node (ref "D1") (pin "3") (pinfunction "3_3") (pintype "bidirectional"))
    )
    (net (code "134") (name "unconnected-(D1-Pad6)") (class "Default")
      (node (ref "D1") (pin "6") (pinfunction "6_6") (pintype "bidirectional"))
    )
    (net (code "135") (name "unconnected-(D23-Pad3)") (class "Default")
      (node (ref "D23") (pin "3") (pinfunction "3_3") (pintype "bidirectional"))
    )
    (net (code "136") (name "unconnected-(D23-Pad6)") (class "Default")
      (node (ref "D23") (pin "6") (pinfunction "6_6") (pintype "bidirectional"))
    )
    (net (code "137") (name "unconnected-(J3-Pad30)") (class "Default")
      (node (ref "J3") (pin "30") (pinfunction "30_30") (pintype "passive"))
    )
    (net (code "138") (name "unconnected-(J3-Pad32)") (class "Default")
      (node (ref "J3") (pin "32") (pinfunction "32_32") (pintype "passive"))
    )
    (net (code "139") (name "unconnected-(J11-5-PadNC1)") (class "Default")
      (node (ref "J11") (pin "NC1") (pinfunction "5_NC1") (pintype "bidirectional"))
    )
    (net (code "140") (name "unconnected-(J11-6-PadNC2)") (class "Default")
      (node (ref "J11") (pin "NC2") (pinfunction "6_NC2") (pintype "bidirectional"))
    )
    (net (code "141") (name "unconnected-(J13-VPP-PadC6)") (class "Default")
      (node (ref "J13") (pin "C6") (pinfunction "VPP_C6") (pintype "passive"))
    )
    (net (code "142") (name "unconnected-(JTAG-Pad7)") (class "Default")
      (node (ref "JTAG") (pin "7") (pinfunction "7_7") (pintype "bidirectional"))
    )
    (net (code "143") (name "unconnected-(JTAG-Pad8)") (class "Default")
      (node (ref "JTAG") (pin "8") (pinfunction "8_8") (pintype "bidirectional"))
    )
    (net (code "144") (name "unconnected-(U1-FLG-Pad3)") (class "Default")
      (node (ref "U1") (pin "3") (pinfunction "FLG_3") (pintype "bidirectional"))
    )
    (net (code "145") (name "unconnected-(U7-NA1-Pad4)") (class "Default")
      (node (ref "U7") (pin "4") (pinfunction "NA1_4") (pintype "bidirectional"))
    )
    (net (code "146") (name "unconnected-(U7-NA2-Pad5)") (class "Default")
      (node (ref "U7") (pin "5") (pinfunction "NA2_5") (pintype "bidirectional"))
    )
    (net (code "147") (name "unconnected-(X1-Pad1)") (class "Default")
      (node (ref "X1") (pin "1") (pinfunction "1_1") (pintype "passive"))
    )
    (net (code "148") (name "unconnected-(X2-Pad1)") (class "Default")
      (node (ref "X2") (pin "1") (pinfunction "1_1") (pintype "passive"))
    )
    (net (code "149") (name "unconnected-(X3-Pad1)") (class "Default")
      (node (ref "X3") (pin "1") (pinfunction "1_1") (pintype "passive"))
    )
    (net (code "150") (name "~{MODE}") (class "Default")
      (node (ref "J18") (pin "32") (pinfunction "~{MODE}_32") (pintype "bidirectional"))
      (node (ref "J3") (pin "18") (pinfunction "18_18") (pintype "passive"))
      (node (ref "MODE") (pin "3") (pinfunction "3_3") (pintype "passive"))
      (node (ref "MODE") (pin "4") (pinfunction "4_4") (pintype "passive"))
      (node (ref "R12") (pin "1") (pinfunction "1_1") (pintype "passive"))
    )
    (net (code "151") (name "~{RESET}") (class "Default")
      (node (ref "C1") (pin "1") (pinfunction "1_1") (pintype "passive"))
      (node (ref "J18") (pin "!RESET") (pinfunction "~{RESET}_!RESET") (pintype "power_in"))
      (node (ref "J18") (pin "34") (pinfunction "~{RESET}_34") (pintype "bidirectional"))
      (node (ref "J3") (pin "20") (pinfunction "20_20") (pintype "passive"))
      (node (ref "J6") (pin "23") (pinfunction "~{RST}_23") (pintype "passive"))
      (node (ref "J6") (pin "@23") (pinfunction "~{RST}_@23") (pintype "passive"))
      (node (ref "J6") (pin "P$23") (pinfunction "~{RST}_P$23") (pintype "passive"))
      (node (ref "JP5") (pin "1") (pinfunction "1_1") (pintype "passive"))
      (node (ref "JTAG") (pin "10") (pinfunction "10_10") (pintype "bidirectional"))
      (node (ref "R4") (pin "1") (pinfunction "1_1") (pintype "passive"))
      (node (ref "RESET") (pin "3") (pinfunction "3_3") (pintype "passive"))
      (node (ref "RESET") (pin "4") (pinfunction "4_4") (pintype "passive"))
    )
  )
)
